# 20230322.net
KiCad netlist of a schematic drawn in EAGLE
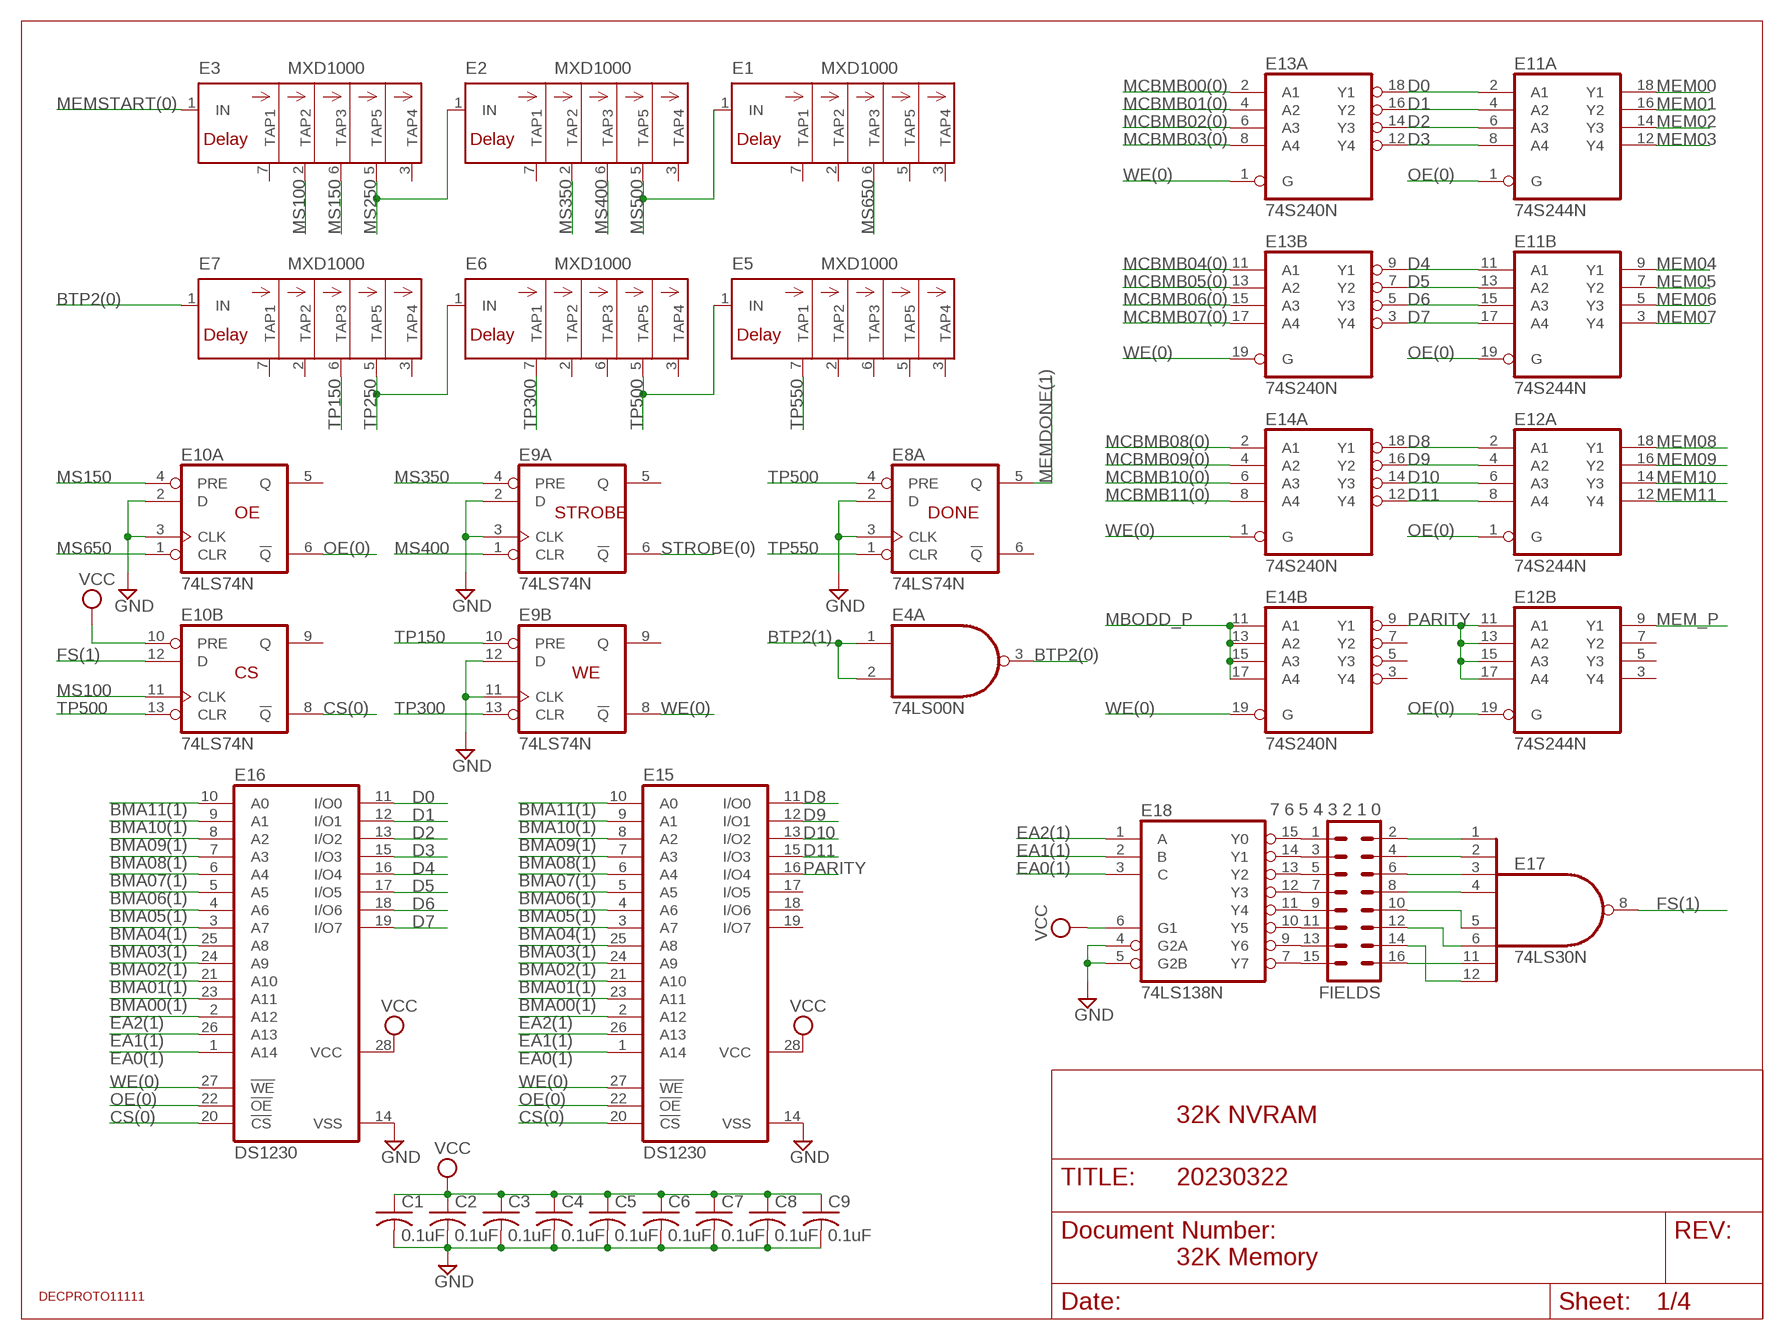
[diagram p0: schematic, sheet 1]
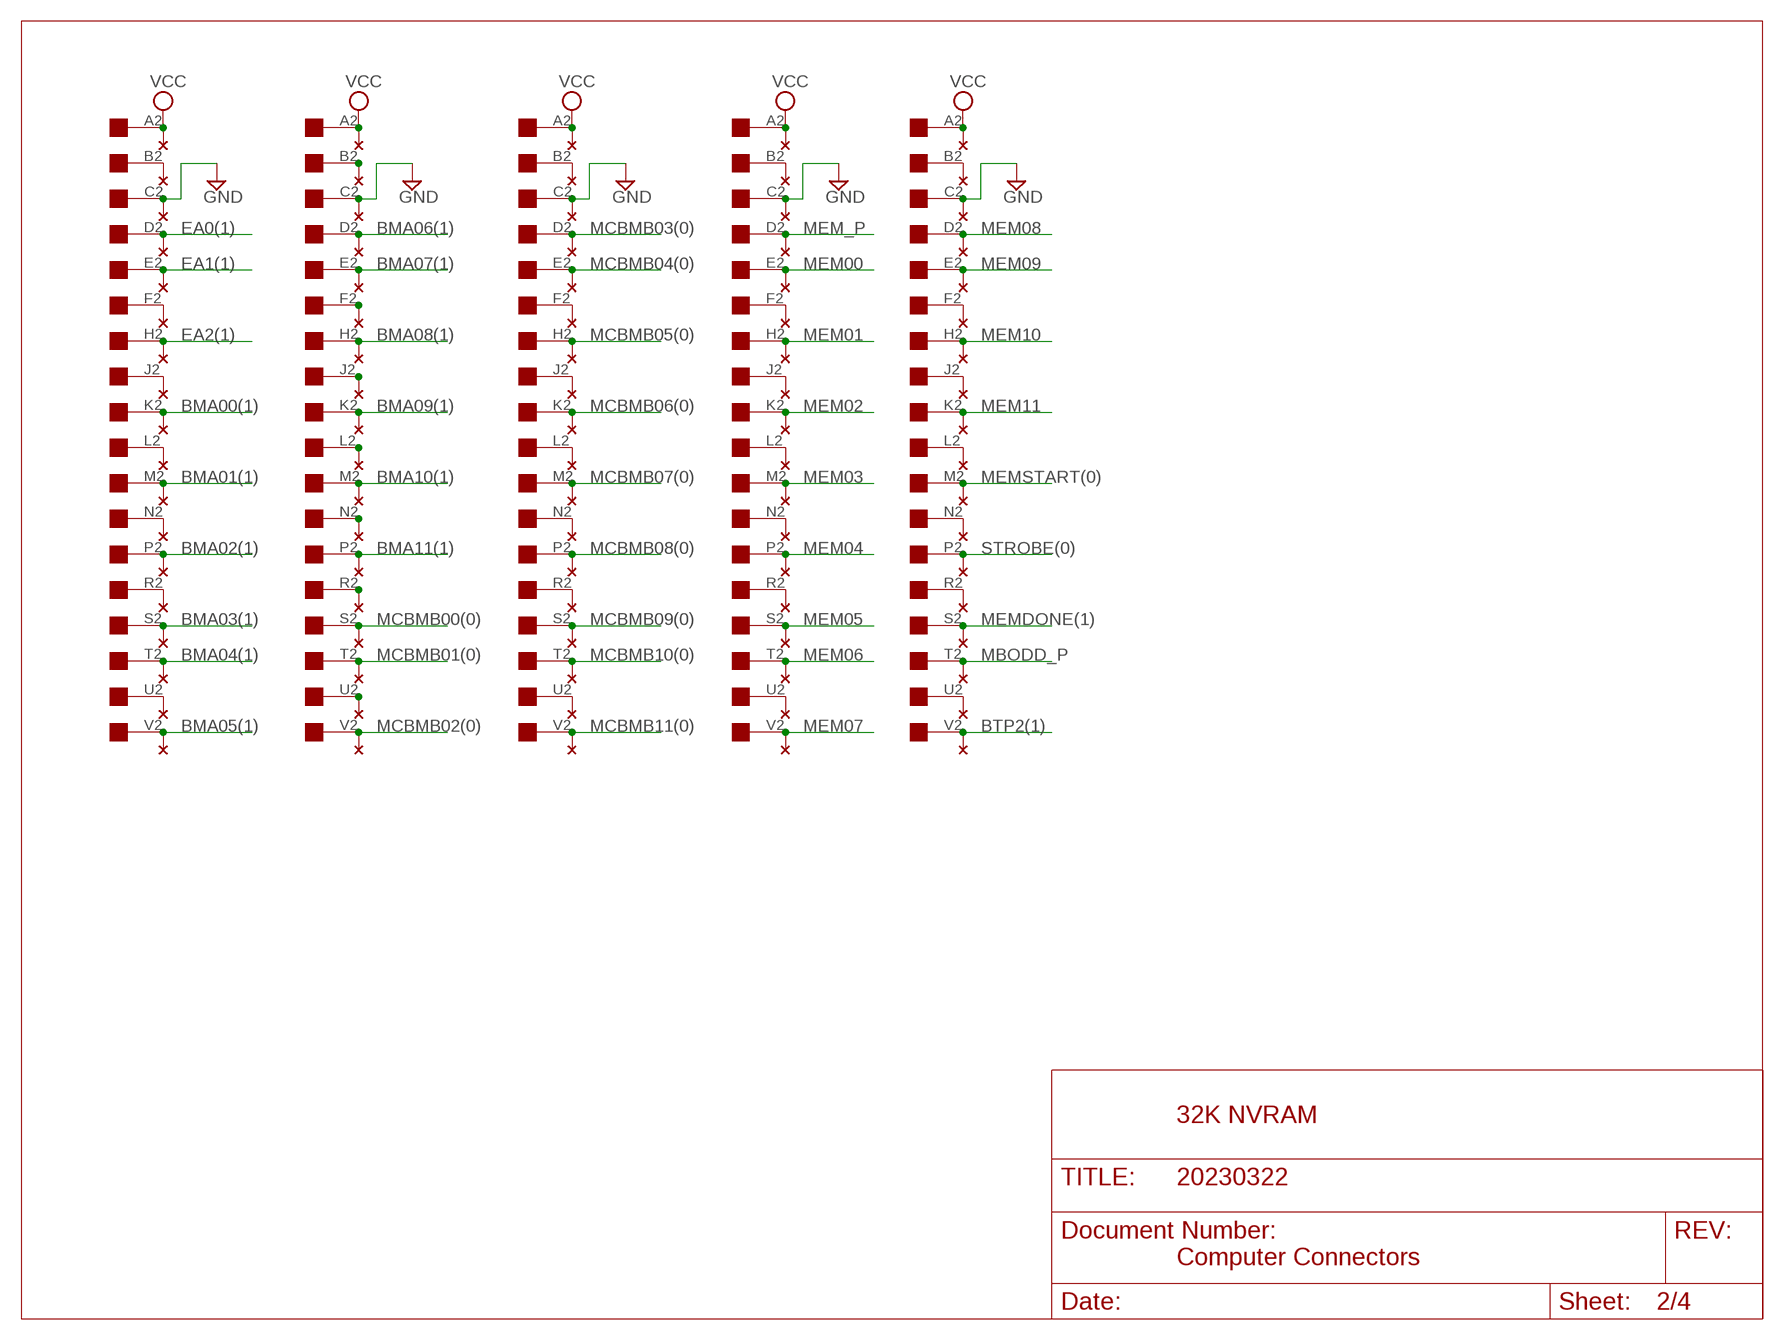
[diagram p1: schematic, sheet 2]
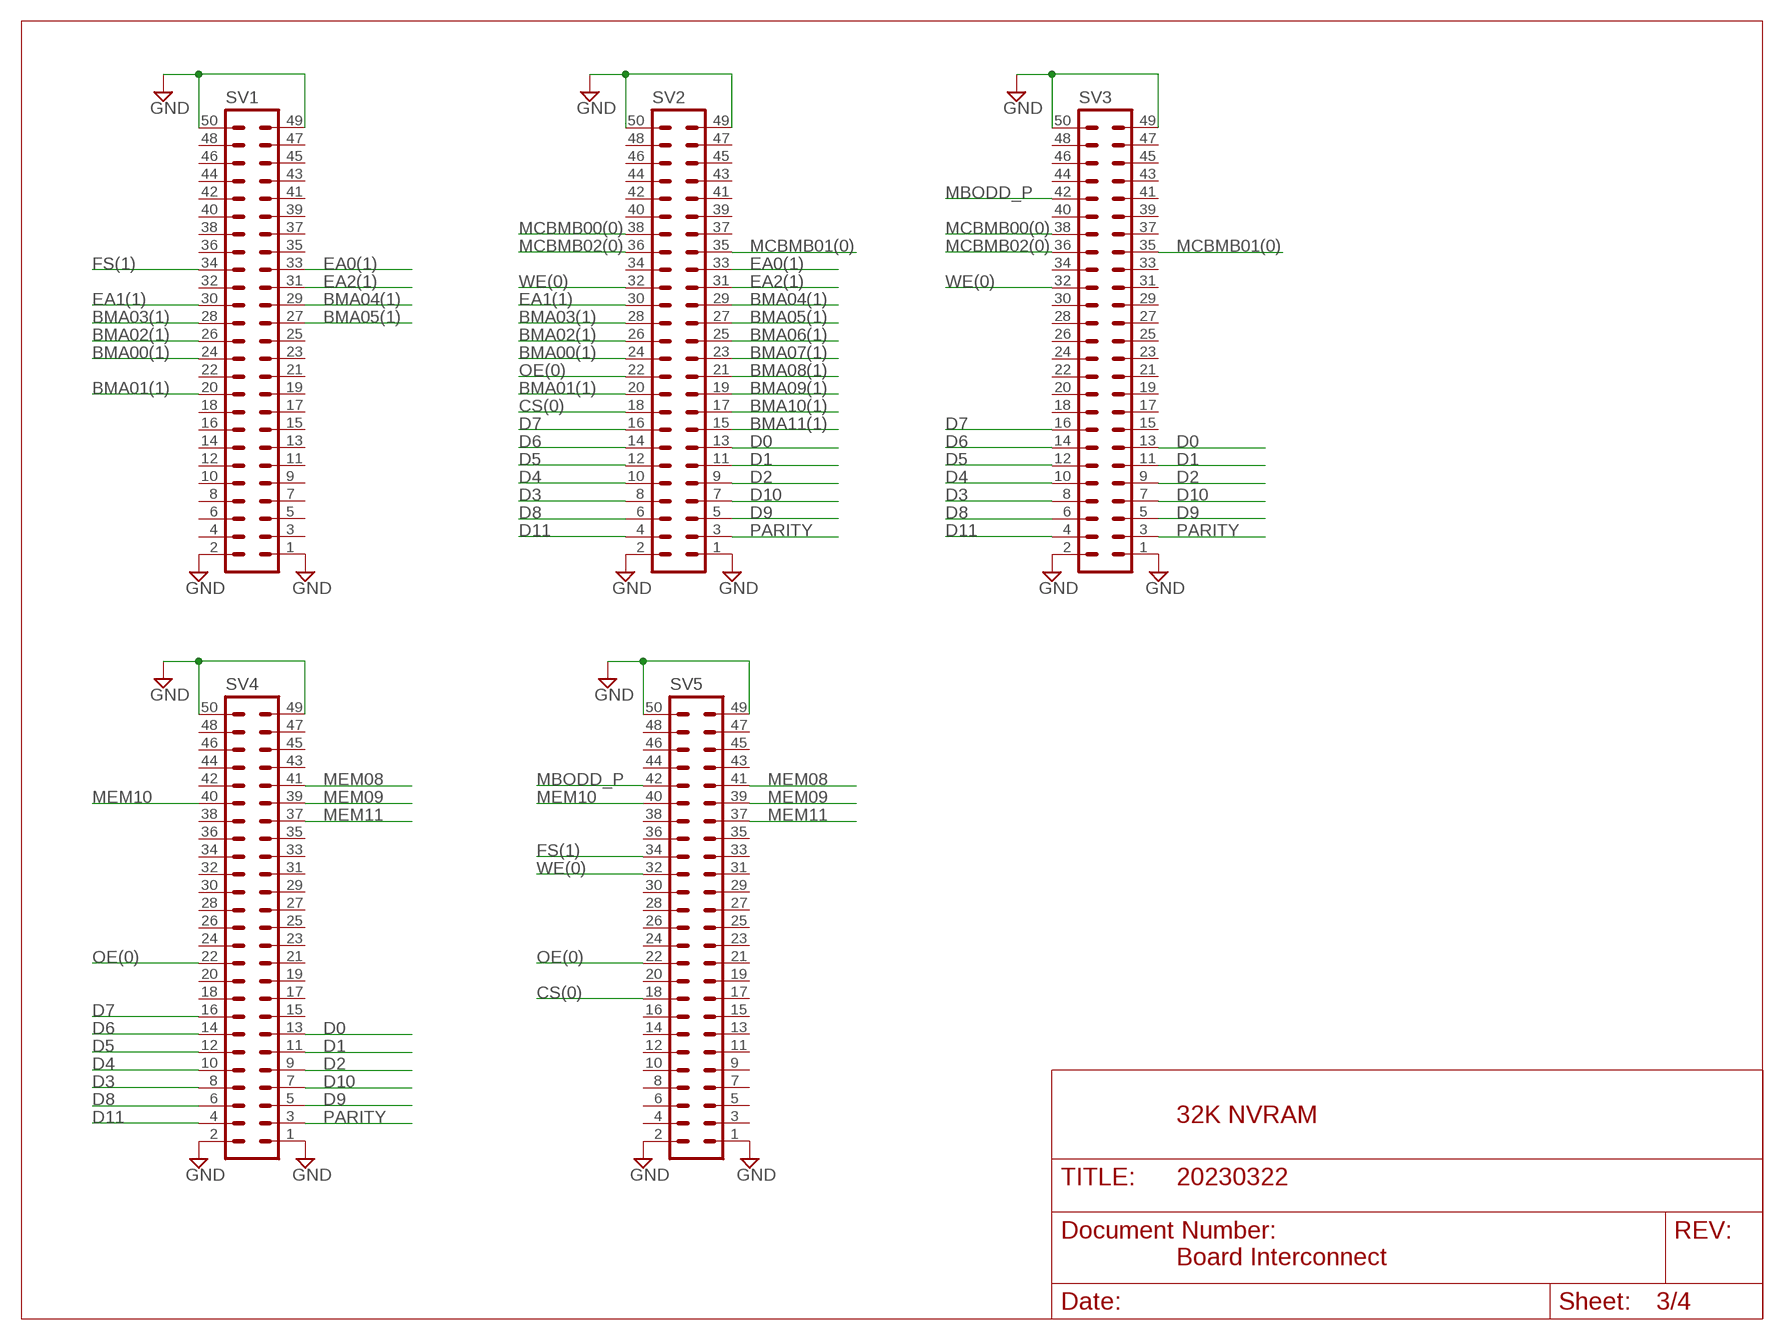
[diagram p2: schematic, sheet 3]
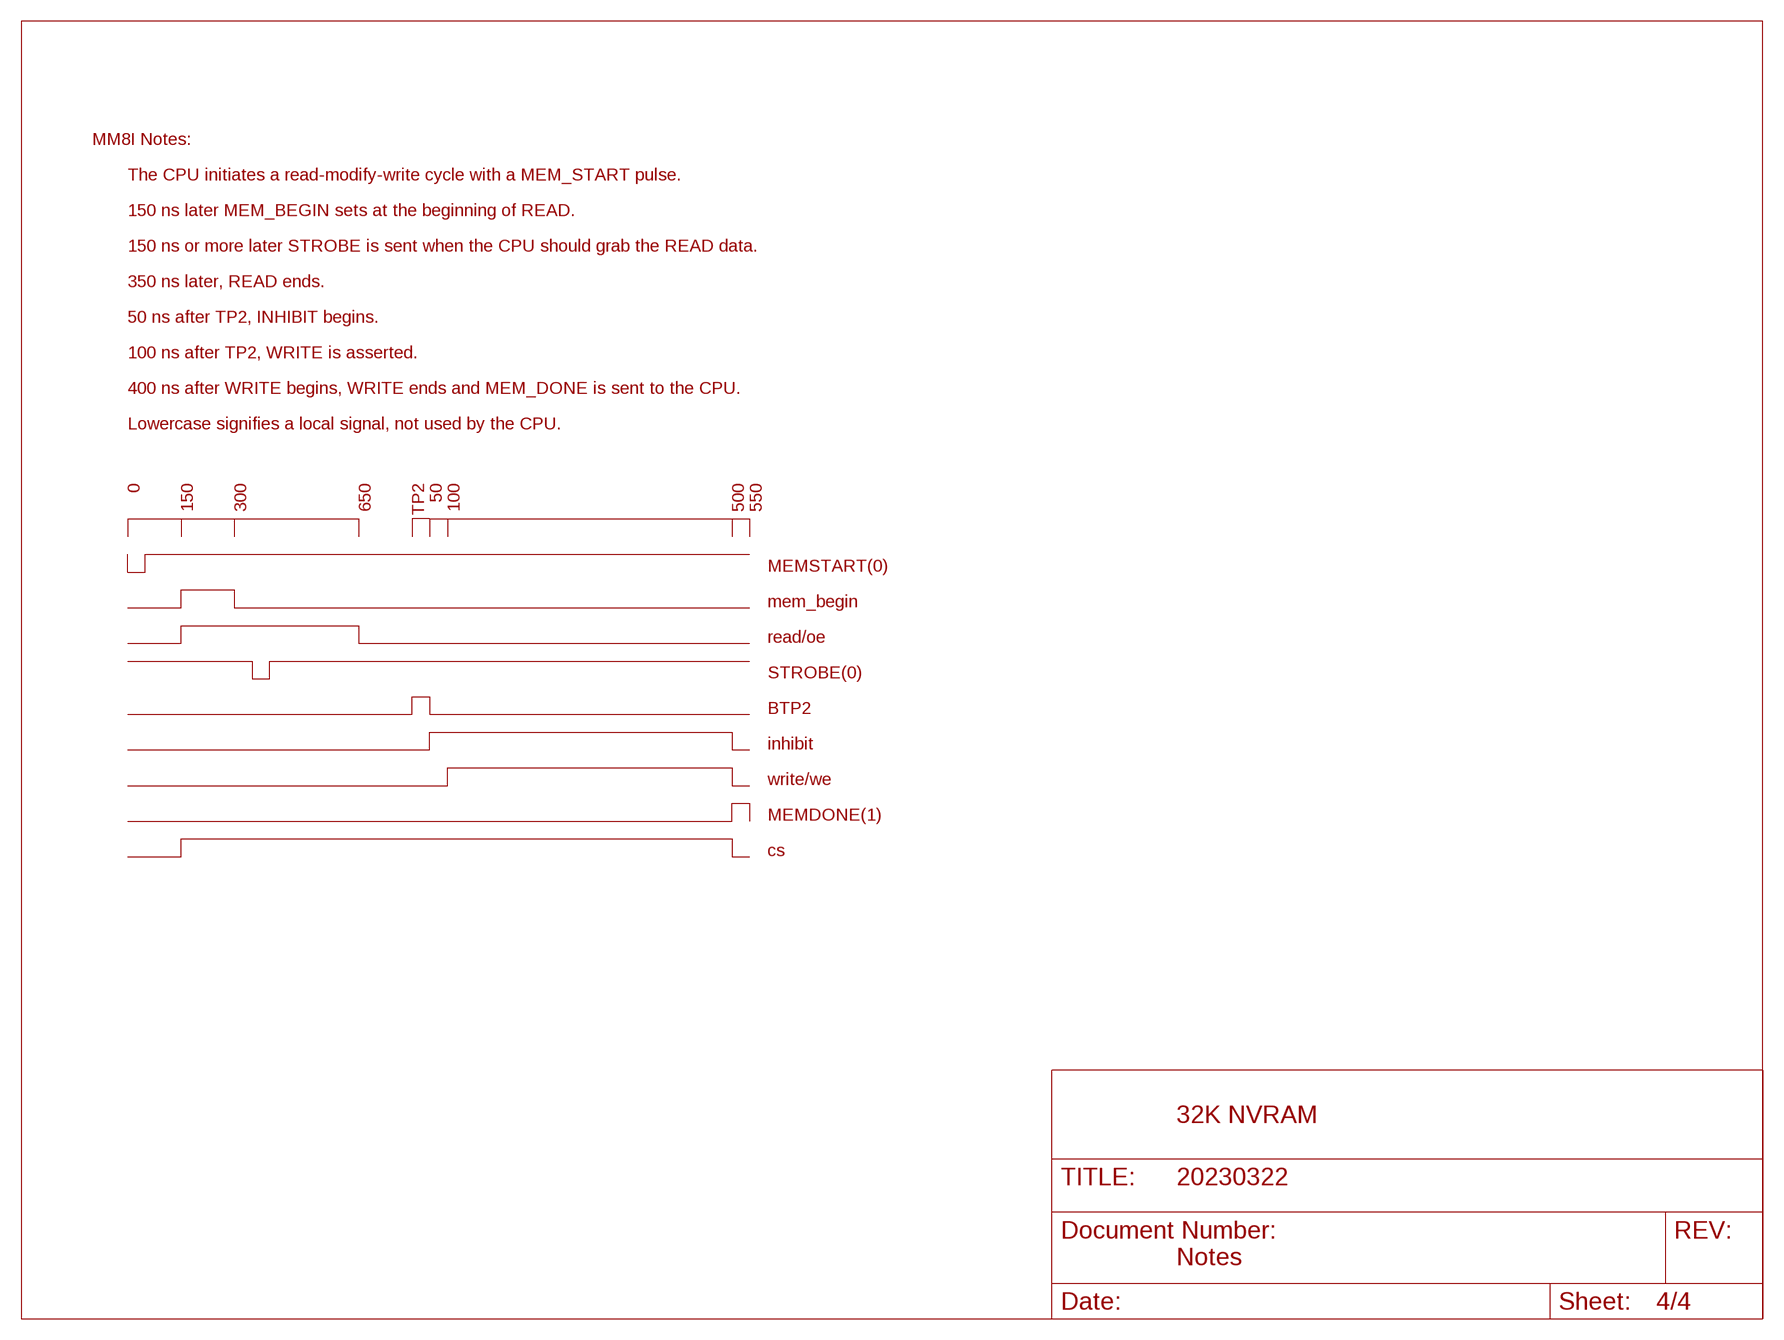
[diagram p3: schematic, sheet 4]

(export (version "E")
  (design (tool "Eeschema 10.0.6"))
  (components
    (comp (ref "H01")
      (value "EDGE-1")
      (footprint "eagle-import:EDGE-CON1")
      (libsource (lib "eagle-import") (part "EDGE-1"))
    )
    (comp (ref "H02")
      (value "EDGE-1")
      (footprint "eagle-import:EDGE-CON1")
      (libsource (lib "eagle-import") (part "EDGE-1"))
    )
    (comp (ref "H03")
      (value "EDGE-1")
      (footprint "eagle-import:EDGE-CON1")
      (libsource (lib "eagle-import") (part "EDGE-1"))
    )
    (comp (ref "H04")
      (value "EDGE-1")
      (footprint "eagle-import:EDGE-CON1")
      (libsource (lib "eagle-import") (part "EDGE-1"))
    )
    (comp (ref "H05")
      (value "EDGE-1")
      (footprint "eagle-import:EDGE-CON1")
      (libsource (lib "eagle-import") (part "EDGE-1"))
    )
    (comp (ref "U$1")
      (value "THRU-HOLE2")
      (footprint "eagle-import:THRU-HOLEB")
      (libsource (lib "eagle-import") (part "THRU-HOLE2"))
    )
    (comp (ref "U$2")
      (value "THRU-HOLE2")
      (footprint "eagle-import:THRU-HOLEB")
      (libsource (lib "eagle-import") (part "THRU-HOLE2"))
    )
    (comp (ref "U$3")
      (value "THRU-HOLE2")
      (footprint "eagle-import:THRU-HOLEB")
      (libsource (lib "eagle-import") (part "THRU-HOLE2"))
    )
    (comp (ref "U$4")
      (value "THRU-HOLE2")
      (footprint "eagle-import:THRU-HOLEB")
      (libsource (lib "eagle-import") (part "THRU-HOLE2"))
    )
    (comp (ref "U$5")
      (value "THRU-HOLE2")
      (footprint "eagle-import:THRU-HOLEB")
      (libsource (lib "eagle-import") (part "THRU-HOLE2"))
    )
    (comp (ref "SV1")
      (value "ML50L")
      (footprint "eagle-import:ML50L")
      (libsource (lib "eagle-import") (part "ML50L"))
    )
    (comp (ref "SV2")
      (value "ML50L")
      (footprint "eagle-import:ML50L")
      (libsource (lib "eagle-import") (part "ML50L"))
    )
    (comp (ref "SV3")
      (value "ML50L")
      (footprint "eagle-import:ML50L")
      (libsource (lib "eagle-import") (part "ML50L"))
    )
    (comp (ref "SV4")
      (value "ML50L")
      (footprint "eagle-import:ML50L")
      (libsource (lib "eagle-import") (part "ML50L"))
    )
    (comp (ref "SV5")
      (value "ML50L")
      (footprint "eagle-import:ML50L")
      (libsource (lib "eagle-import") (part "ML50L"))
    )
    (comp (ref "C1")
      (value "0.1uF")
      (footprint "eagle-import:C050-025X075")
      (libsource (lib "eagle-import") (part "C-US050-025X075"))
    )
    (comp (ref "C2")
      (value "0.1uF")
      (footprint "eagle-import:C050-025X075")
      (libsource (lib "eagle-import") (part "C-US050-025X075"))
    )
    (comp (ref "C3")
      (value "0.1uF")
      (footprint "eagle-import:C050-025X075")
      (libsource (lib "eagle-import") (part "C-US050-025X075"))
    )
    (comp (ref "C4")
      (value "0.1uF")
      (footprint "eagle-import:C050-025X075")
      (libsource (lib "eagle-import") (part "C-US050-025X075"))
    )
    (comp (ref "C5")
      (value "0.1uF")
      (footprint "eagle-import:C050-025X075")
      (libsource (lib "eagle-import") (part "C-US050-025X075"))
    )
    (comp (ref "C6")
      (value "0.1uF")
      (footprint "eagle-import:C050-025X075")
      (libsource (lib "eagle-import") (part "C-US050-025X075"))
    )
    (comp (ref "C7")
      (value "0.1uF")
      (footprint "eagle-import:C050-025X075")
      (libsource (lib "eagle-import") (part "C-US050-025X075"))
    )
    (comp (ref "C8")
      (value "0.1uF")
      (footprint "eagle-import:C050-025X075")
      (libsource (lib "eagle-import") (part "C-US050-025X075"))
    )
    (comp (ref "C9")
      (value "0.1uF")
      (footprint "eagle-import:C050-025X075")
      (libsource (lib "eagle-import") (part "C-US050-025X075"))
    )
    (comp (ref "E1")
      (value "MXD1000")
      (footprint "eagle-import:DIL08")
      (libsource (lib "eagle-import") (part "MXD1000"))
    )
    (comp (ref "E2")
      (value "MXD1000")
      (footprint "eagle-import:DIL08")
      (libsource (lib "eagle-import") (part "MXD1000"))
    )
    (comp (ref "E3")
      (value "MXD1000")
      (footprint "eagle-import:DIL08")
      (libsource (lib "eagle-import") (part "MXD1000"))
    )
    (comp (ref "E4")
      (value "74LS00N")
      (footprint "eagle-import:DIL14")
      (libsource (lib "eagle-import") (part "7400NLS"))
    )
    (comp (ref "E5")
      (value "MXD1000")
      (footprint "eagle-import:DIL08")
      (libsource (lib "eagle-import") (part "MXD1000"))
    )
    (comp (ref "E6")
      (value "MXD1000")
      (footprint "eagle-import:DIL08")
      (libsource (lib "eagle-import") (part "MXD1000"))
    )
    (comp (ref "E7")
      (value "MXD1000")
      (footprint "eagle-import:DIL08")
      (libsource (lib "eagle-import") (part "MXD1000"))
    )
    (comp (ref "E8")
      (value "74LS74N")
      (footprint "eagle-import:DIL14")
      (libsource (lib "eagle-import") (part "7474NLS"))
    )
    (comp (ref "E9")
      (value "74LS74N")
      (footprint "eagle-import:DIL14")
      (libsource (lib "eagle-import") (part "7474NLS"))
    )
    (comp (ref "E10")
      (value "74LS74N")
      (footprint "eagle-import:DIL14")
      (libsource (lib "eagle-import") (part "7474NLS"))
    )
    (comp (ref "E11")
      (value "74S244N")
      (footprint "eagle-import:DIL20")
      (libsource (lib "eagle-import") (part "74244NS"))
    )
    (comp (ref "E12")
      (value "74S244N")
      (footprint "eagle-import:DIL20")
      (libsource (lib "eagle-import") (part "74244NS"))
    )
    (comp (ref "E13")
      (value "74S240N")
      (footprint "eagle-import:DIL20")
      (libsource (lib "eagle-import") (part "74240NS"))
    )
    (comp (ref "E14")
      (value "74S240N")
      (footprint "eagle-import:DIL20")
      (libsource (lib "eagle-import") (part "74240NS"))
    )
    (comp (ref "E15")
      (value "DS1230")
      (footprint "eagle-import:DIL28-6")
      (libsource (lib "eagle-import") (part "62256P"))
    )
    (comp (ref "E16")
      (value "DS1230")
      (footprint "eagle-import:DIL28-6")
      (libsource (lib "eagle-import") (part "62256P"))
    )
    (comp (ref "E17")
      (value "74LS30N")
      (footprint "eagle-import:DIL14")
      (libsource (lib "eagle-import") (part "7430NLS"))
    )
    (comp (ref "E18")
      (value "74LS138N")
      (footprint "eagle-import:DIL16")
      (libsource (lib "eagle-import") (part "74138NLS"))
    )
    (comp (ref "FIELDS")
      (value "7 6 5 4 3 2 1 0")
      (footprint "eagle-import:MA08-2")
      (libsource (lib "eagle-import") (part "MA08-2"))
    )
    (comp (ref "U$6")
      (value "DECPROTO11111")
      (footprint "eagle-import:DECPROTO11111")
      (libsource (lib "eagle-import") (part "DECPROTO11111"))
    )
  )
  (nets
    (net (code "1") (name "BMA00(1)") (class "Default")
      (node (ref "E15") (pin "23") (pinfunction "A11_23") (pintype "input"))
      (node (ref "E16") (pin "23") (pinfunction "A11_23") (pintype "input"))
      (node (ref "H01") (pin "K2") (pinfunction "1_K2") (pintype "bidirectional"))
      (node (ref "SV1") (pin "24") (pinfunction "24_24") (pintype "passive"))
      (node (ref "SV2") (pin "24") (pinfunction "24_24") (pintype "passive"))
      (node (ref "U$1") (pin "K2") (pinfunction "P$1_K2") (pintype "passive"))
    )
    (net (code "2") (name "BMA01(1)") (class "Default")
      (node (ref "E15") (pin "21") (pinfunction "A10_21") (pintype "input"))
      (node (ref "E16") (pin "21") (pinfunction "A10_21") (pintype "input"))
      (node (ref "H01") (pin "M2") (pinfunction "1_M2") (pintype "bidirectional"))
      (node (ref "SV1") (pin "20") (pinfunction "20_20") (pintype "passive"))
      (node (ref "SV2") (pin "20") (pinfunction "20_20") (pintype "passive"))
      (node (ref "U$1") (pin "M2") (pinfunction "P$1_M2") (pintype "passive"))
    )
    (net (code "3") (name "BMA02(1)") (class "Default")
      (node (ref "E15") (pin "24") (pinfunction "A9_24") (pintype "input"))
      (node (ref "E16") (pin "24") (pinfunction "A9_24") (pintype "input"))
      (node (ref "H01") (pin "P2") (pinfunction "1_P2") (pintype "bidirectional"))
      (node (ref "SV1") (pin "26") (pinfunction "26_26") (pintype "passive"))
      (node (ref "SV2") (pin "26") (pinfunction "26_26") (pintype "passive"))
      (node (ref "U$1") (pin "P2") (pinfunction "P$1_P2") (pintype "passive"))
    )
    (net (code "4") (name "BMA03(1)") (class "Default")
      (node (ref "E15") (pin "25") (pinfunction "A8_25") (pintype "input"))
      (node (ref "E16") (pin "25") (pinfunction "A8_25") (pintype "input"))
      (node (ref "H01") (pin "S2") (pinfunction "1_S2") (pintype "bidirectional"))
      (node (ref "SV1") (pin "28") (pinfunction "28_28") (pintype "passive"))
      (node (ref "SV2") (pin "28") (pinfunction "28_28") (pintype "passive"))
      (node (ref "U$1") (pin "S2") (pinfunction "P$1_S2") (pintype "passive"))
    )
    (net (code "5") (name "BMA04(1)") (class "Default")
      (node (ref "E15") (pin "3") (pinfunction "A7_3") (pintype "input"))
      (node (ref "E16") (pin "3") (pinfunction "A7_3") (pintype "input"))
      (node (ref "H01") (pin "T2") (pinfunction "1_T2") (pintype "bidirectional"))
      (node (ref "SV1") (pin "29") (pinfunction "29_29") (pintype "passive"))
      (node (ref "SV2") (pin "29") (pinfunction "29_29") (pintype "passive"))
      (node (ref "U$1") (pin "T2") (pinfunction "P$1_T2") (pintype "passive"))
    )
    (net (code "6") (name "BMA05(1)") (class "Default")
      (node (ref "E15") (pin "4") (pinfunction "A6_4") (pintype "input"))
      (node (ref "E16") (pin "4") (pinfunction "A6_4") (pintype "input"))
      (node (ref "H01") (pin "V2") (pinfunction "1_V2") (pintype "bidirectional"))
      (node (ref "SV1") (pin "27") (pinfunction "27_27") (pintype "passive"))
      (node (ref "SV2") (pin "27") (pinfunction "27_27") (pintype "passive"))
      (node (ref "U$1") (pin "V2") (pinfunction "P$1_V2") (pintype "passive"))
    )
    (net (code "7") (name "BMA06(1)") (class "Default")
      (node (ref "E15") (pin "5") (pinfunction "A5_5") (pintype "input"))
      (node (ref "E16") (pin "5") (pinfunction "A5_5") (pintype "input"))
      (node (ref "H02") (pin "D2") (pinfunction "1_D2") (pintype "bidirectional"))
      (node (ref "SV2") (pin "25") (pinfunction "25_25") (pintype "passive"))
      (node (ref "U$2") (pin "D2") (pinfunction "P$1_D2") (pintype "passive"))
    )
    (net (code "8") (name "BMA07(1)") (class "Default")
      (node (ref "E15") (pin "6") (pinfunction "A4_6") (pintype "input"))
      (node (ref "E16") (pin "6") (pinfunction "A4_6") (pintype "input"))
      (node (ref "H02") (pin "E2") (pinfunction "1_E2") (pintype "bidirectional"))
      (node (ref "SV2") (pin "23") (pinfunction "23_23") (pintype "passive"))
      (node (ref "U$2") (pin "E2") (pinfunction "P$1_E2") (pintype "passive"))
    )
    (net (code "9") (name "BMA08(1)") (class "Default")
      (node (ref "E15") (pin "7") (pinfunction "A3_7") (pintype "input"))
      (node (ref "E16") (pin "7") (pinfunction "A3_7") (pintype "input"))
      (node (ref "H02") (pin "H2") (pinfunction "1_H2") (pintype "bidirectional"))
      (node (ref "SV2") (pin "21") (pinfunction "21_21") (pintype "passive"))
      (node (ref "U$2") (pin "H2") (pinfunction "P$1_H2") (pintype "passive"))
    )
    (net (code "10") (name "BMA09(1)") (class "Default")
      (node (ref "E15") (pin "8") (pinfunction "A2_8") (pintype "input"))
      (node (ref "E16") (pin "8") (pinfunction "A2_8") (pintype "input"))
      (node (ref "H02") (pin "K2") (pinfunction "1_K2") (pintype "bidirectional"))
      (node (ref "SV2") (pin "19") (pinfunction "19_19") (pintype "passive"))
      (node (ref "U$2") (pin "K2") (pinfunction "P$1_K2") (pintype "passive"))
    )
    (net (code "11") (name "BMA10(1)") (class "Default")
      (node (ref "E15") (pin "9") (pinfunction "A1_9") (pintype "input"))
      (node (ref "E16") (pin "9") (pinfunction "A1_9") (pintype "input"))
      (node (ref "H02") (pin "M2") (pinfunction "1_M2") (pintype "bidirectional"))
      (node (ref "SV2") (pin "17") (pinfunction "17_17") (pintype "passive"))
      (node (ref "U$2") (pin "M2") (pinfunction "P$1_M2") (pintype "passive"))
    )
    (net (code "12") (name "BMA11(1)") (class "Default")
      (node (ref "E15") (pin "10") (pinfunction "A0_10") (pintype "input"))
      (node (ref "E16") (pin "10") (pinfunction "A0_10") (pintype "input"))
      (node (ref "H02") (pin "P2") (pinfunction "1_P2") (pintype "bidirectional"))
      (node (ref "SV2") (pin "15") (pinfunction "15_15") (pintype "passive"))
      (node (ref "U$2") (pin "P2") (pinfunction "P$1_P2") (pintype "passive"))
    )
    (net (code "13") (name "BTP2(0)") (class "Default")
      (node (ref "E4") (pin "3") (pinfunction "O_3") (pintype "output"))
      (node (ref "E7") (pin "1") (pinfunction "IN_1") (pintype "input"))
    )
    (net (code "14") (name "BTP2(1)") (class "Default")
      (node (ref "E4") (pin "1") (pinfunction "I0_1") (pintype "input"))
      (node (ref "E4") (pin "2") (pinfunction "I1_2") (pintype "input"))
      (node (ref "H05") (pin "V2") (pinfunction "1_V2") (pintype "bidirectional"))
      (node (ref "U$5") (pin "V2") (pinfunction "P$1_V2") (pintype "passive"))
    )
    (net (code "15") (name "CS(0)") (class "Default")
      (node (ref "E10") (pin "8") (pinfunction "~{Q}_8") (pintype "output"))
      (node (ref "E15") (pin "20") (pinfunction "~{CS}_20") (pintype "input"))
      (node (ref "E16") (pin "20") (pinfunction "~{CS}_20") (pintype "input"))
      (node (ref "SV2") (pin "18") (pinfunction "18_18") (pintype "passive"))
      (node (ref "SV5") (pin "18") (pinfunction "18_18") (pintype "passive"))
    )
    (net (code "16") (name "D0") (class "Default")
      (node (ref "E11") (pin "2") (pinfunction "A1_2") (pintype "input"))
      (node (ref "E13") (pin "18") (pinfunction "Y1_18") (pintype "tri_state"))
      (node (ref "E16") (pin "11") (pinfunction "I/O0_11") (pintype "bidirectional"))
      (node (ref "SV2") (pin "13") (pinfunction "13_13") (pintype "passive"))
      (node (ref "SV3") (pin "13") (pinfunction "13_13") (pintype "passive"))
      (node (ref "SV4") (pin "13") (pinfunction "13_13") (pintype "passive"))
    )
    (net (code "17") (name "D1") (class "Default")
      (node (ref "E11") (pin "4") (pinfunction "A2_4") (pintype "input"))
      (node (ref "E13") (pin "16") (pinfunction "Y2_16") (pintype "tri_state"))
      (node (ref "E16") (pin "12") (pinfunction "I/O1_12") (pintype "bidirectional"))
      (node (ref "SV2") (pin "11") (pinfunction "11_11") (pintype "passive"))
      (node (ref "SV3") (pin "11") (pinfunction "11_11") (pintype "passive"))
      (node (ref "SV4") (pin "11") (pinfunction "11_11") (pintype "passive"))
    )
    (net (code "18") (name "D2") (class "Default")
      (node (ref "E11") (pin "6") (pinfunction "A3_6") (pintype "input"))
      (node (ref "E13") (pin "14") (pinfunction "Y3_14") (pintype "tri_state"))
      (node (ref "E16") (pin "13") (pinfunction "I/O2_13") (pintype "bidirectional"))
      (node (ref "SV2") (pin "9") (pinfunction "9_9") (pintype "passive"))
      (node (ref "SV3") (pin "9") (pinfunction "9_9") (pintype "passive"))
      (node (ref "SV4") (pin "9") (pinfunction "9_9") (pintype "passive"))
    )
    (net (code "19") (name "D3") (class "Default")
      (node (ref "E11") (pin "8") (pinfunction "A4_8") (pintype "input"))
      (node (ref "E13") (pin "12") (pinfunction "Y4_12") (pintype "tri_state"))
      (node (ref "E16") (pin "15") (pinfunction "I/O3_15") (pintype "bidirectional"))
      (node (ref "SV2") (pin "8") (pinfunction "8_8") (pintype "passive"))
      (node (ref "SV3") (pin "8") (pinfunction "8_8") (pintype "passive"))
      (node (ref "SV4") (pin "8") (pinfunction "8_8") (pintype "passive"))
    )
    (net (code "20") (name "D4") (class "Default")
      (node (ref "E11") (pin "11") (pinfunction "A1_11") (pintype "input"))
      (node (ref "E13") (pin "9") (pinfunction "Y1_9") (pintype "tri_state"))
      (node (ref "E16") (pin "16") (pinfunction "I/O4_16") (pintype "bidirectional"))
      (node (ref "SV2") (pin "10") (pinfunction "10_10") (pintype "passive"))
      (node (ref "SV3") (pin "10") (pinfunction "10_10") (pintype "passive"))
      (node (ref "SV4") (pin "10") (pinfunction "10_10") (pintype "passive"))
    )
    (net (code "21") (name "D5") (class "Default")
      (node (ref "E11") (pin "13") (pinfunction "A2_13") (pintype "input"))
      (node (ref "E13") (pin "7") (pinfunction "Y2_7") (pintype "tri_state"))
      (node (ref "E16") (pin "17") (pinfunction "I/O5_17") (pintype "bidirectional"))
      (node (ref "SV2") (pin "12") (pinfunction "12_12") (pintype "passive"))
      (node (ref "SV3") (pin "12") (pinfunction "12_12") (pintype "passive"))
      (node (ref "SV4") (pin "12") (pinfunction "12_12") (pintype "passive"))
    )
    (net (code "22") (name "D6") (class "Default")
      (node (ref "E11") (pin "15") (pinfunction "A3_15") (pintype "input"))
      (node (ref "E13") (pin "5") (pinfunction "Y3_5") (pintype "tri_state"))
      (node (ref "E16") (pin "18") (pinfunction "I/O6_18") (pintype "bidirectional"))
      (node (ref "SV2") (pin "14") (pinfunction "14_14") (pintype "passive"))
      (node (ref "SV3") (pin "14") (pinfunction "14_14") (pintype "passive"))
      (node (ref "SV4") (pin "14") (pinfunction "14_14") (pintype "passive"))
    )
    (net (code "23") (name "D7") (class "Default")
      (node (ref "E11") (pin "17") (pinfunction "A4_17") (pintype "input"))
      (node (ref "E13") (pin "3") (pinfunction "Y4_3") (pintype "tri_state"))
      (node (ref "E16") (pin "19") (pinfunction "I/O7_19") (pintype "bidirectional"))
      (node (ref "SV2") (pin "16") (pinfunction "16_16") (pintype "passive"))
      (node (ref "SV3") (pin "16") (pinfunction "16_16") (pintype "passive"))
      (node (ref "SV4") (pin "16") (pinfunction "16_16") (pintype "passive"))
    )
    (net (code "24") (name "D8") (class "Default")
      (node (ref "E12") (pin "2") (pinfunction "A1_2") (pintype "input"))
      (node (ref "E14") (pin "18") (pinfunction "Y1_18") (pintype "tri_state"))
      (node (ref "E15") (pin "11") (pinfunction "I/O0_11") (pintype "bidirectional"))
      (node (ref "SV2") (pin "6") (pinfunction "6_6") (pintype "passive"))
      (node (ref "SV3") (pin "6") (pinfunction "6_6") (pintype "passive"))
      (node (ref "SV4") (pin "6") (pinfunction "6_6") (pintype "passive"))
    )
    (net (code "25") (name "D9") (class "Default")
      (node (ref "E12") (pin "4") (pinfunction "A2_4") (pintype "input"))
      (node (ref "E14") (pin "16") (pinfunction "Y2_16") (pintype "tri_state"))
      (node (ref "E15") (pin "12") (pinfunction "I/O1_12") (pintype "bidirectional"))
      (node (ref "SV2") (pin "5") (pinfunction "5_5") (pintype "passive"))
      (node (ref "SV3") (pin "5") (pinfunction "5_5") (pintype "passive"))
      (node (ref "SV4") (pin "5") (pinfunction "5_5") (pintype "passive"))
    )
    (net (code "26") (name "D10") (class "Default")
      (node (ref "E12") (pin "6") (pinfunction "A3_6") (pintype "input"))
      (node (ref "E14") (pin "14") (pinfunction "Y3_14") (pintype "tri_state"))
      (node (ref "E15") (pin "13") (pinfunction "I/O2_13") (pintype "bidirectional"))
      (node (ref "SV2") (pin "7") (pinfunction "7_7") (pintype "passive"))
      (node (ref "SV3") (pin "7") (pinfunction "7_7") (pintype "passive"))
      (node (ref "SV4") (pin "7") (pinfunction "7_7") (pintype "passive"))
    )
    (net (code "27") (name "D11") (class "Default")
      (node (ref "E12") (pin "8") (pinfunction "A4_8") (pintype "input"))
      (node (ref "E14") (pin "12") (pinfunction "Y4_12") (pintype "tri_state"))
      (node (ref "E15") (pin "15") (pinfunction "I/O3_15") (pintype "bidirectional"))
      (node (ref "SV2") (pin "4") (pinfunction "4_4") (pintype "passive"))
      (node (ref "SV3") (pin "4") (pinfunction "4_4") (pintype "passive"))
      (node (ref "SV4") (pin "4") (pinfunction "4_4") (pintype "passive"))
    )
    (net (code "28") (name "EA0(1)") (class "Default")
      (node (ref "E15") (pin "1") (pinfunction "A14_1") (pintype "input"))
      (node (ref "E16") (pin "1") (pinfunction "A14_1") (pintype "input"))
      (node (ref "E18") (pin "3") (pinfunction "C_3") (pintype "input"))
      (node (ref "H01") (pin "D2") (pinfunction "1_D2") (pintype "bidirectional"))
      (node (ref "SV1") (pin "33") (pinfunction "33_33") (pintype "passive"))
      (node (ref "SV2") (pin "33") (pinfunction "33_33") (pintype "passive"))
      (node (ref "U$1") (pin "D2") (pinfunction "P$1_D2") (pintype "passive"))
    )
    (net (code "29") (name "EA1(1)") (class "Default")
      (node (ref "E15") (pin "26") (pinfunction "A13_26") (pintype "input"))
      (node (ref "E16") (pin "26") (pinfunction "A13_26") (pintype "input"))
      (node (ref "E18") (pin "2") (pinfunction "B_2") (pintype "input"))
      (node (ref "H01") (pin "E2") (pinfunction "1_E2") (pintype "bidirectional"))
      (node (ref "SV1") (pin "30") (pinfunction "30_30") (pintype "passive"))
      (node (ref "SV2") (pin "30") (pinfunction "30_30") (pintype "passive"))
      (node (ref "U$1") (pin "E2") (pinfunction "P$1_E2") (pintype "passive"))
    )
    (net (code "30") (name "EA2(1)") (class "Default")
      (node (ref "E15") (pin "2") (pinfunction "A12_2") (pintype "input"))
      (node (ref "E16") (pin "2") (pinfunction "A12_2") (pintype "input"))
      (node (ref "E18") (pin "1") (pinfunction "A_1") (pintype "input"))
      (node (ref "H01") (pin "H2") (pinfunction "1_H2") (pintype "bidirectional"))
      (node (ref "SV1") (pin "31") (pinfunction "31_31") (pintype "passive"))
      (node (ref "SV2") (pin "31") (pinfunction "31_31") (pintype "passive"))
      (node (ref "U$1") (pin "H2") (pinfunction "P$1_H2") (pintype "passive"))
    )
    (net (code "31") (name "FS(1)") (class "Default")
      (node (ref "E10") (pin "12") (pinfunction "D_12") (pintype "input"))
      (node (ref "E17") (pin "8") (pinfunction "O_8") (pintype "output"))
      (node (ref "SV1") (pin "34") (pinfunction "34_34") (pintype "passive"))
      (node (ref "SV5") (pin "34") (pinfunction "34_34") (pintype "passive"))
    )
    (net (code "32") (name "GND") (class "Default")
      (node (ref "C1") (pin "2") (pinfunction "2_2") (pintype "passive"))
      (node (ref "C2") (pin "2") (pinfunction "2_2") (pintype "passive"))
      (node (ref "C3") (pin "2") (pinfunction "2_2") (pintype "passive"))
      (node (ref "C4") (pin "2") (pinfunction "2_2") (pintype "passive"))
      (node (ref "C5") (pin "2") (pinfunction "2_2") (pintype "passive"))
      (node (ref "C6") (pin "2") (pinfunction "2_2") (pintype "passive"))
      (node (ref "C7") (pin "2") (pinfunction "2_2") (pintype "passive"))
      (node (ref "C8") (pin "2") (pinfunction "2_2") (pintype "passive"))
      (node (ref "C9") (pin "2") (pinfunction "2_2") (pintype "passive"))
      (node (ref "E10") (pin "2") (pinfunction "D_2") (pintype "input"))
      (node (ref "E10") (pin "3") (pinfunction "CLK_3") (pintype "input"))
      (node (ref "E15") (pin "14") (pinfunction "VSS_14") (pintype "power_in"))
      (node (ref "E16") (pin "14") (pinfunction "VSS_14") (pintype "power_in"))
      (node (ref "E18") (pin "4") (pinfunction "G2A_4") (pintype "input"))
      (node (ref "E18") (pin "5") (pinfunction "G2B_5") (pintype "input"))
      (node (ref "E8") (pin "2") (pinfunction "D_2") (pintype "input"))
      (node (ref "E8") (pin "3") (pinfunction "CLK_3") (pintype "input"))
      (node (ref "E9") (pin "11") (pinfunction "CLK_11") (pintype "input"))
      (node (ref "E9") (pin "12") (pinfunction "D_12") (pintype "input"))
      (node (ref "E9") (pin "2") (pinfunction "D_2") (pintype "input"))
      (node (ref "E9") (pin "3") (pinfunction "CLK_3") (pintype "input"))
      (node (ref "H01") (pin "C2") (pinfunction "1_C2") (pintype "bidirectional"))
      (node (ref "H02") (pin "C2") (pinfunction "1_C2") (pintype "bidirectional"))
      (node (ref "H03") (pin "C2") (pinfunction "1_C2") (pintype "bidirectional"))
      (node (ref "H04") (pin "C2") (pinfunction "1_C2") (pintype "bidirectional"))
      (node (ref "H05") (pin "C2") (pinfunction "1_C2") (pintype "bidirectional"))
      (node (ref "SV1") (pin "1") (pinfunction "1_1") (pintype "passive"))
      (node (ref "SV1") (pin "2") (pinfunction "2_2") (pintype "passive"))
      (node (ref "SV1") (pin "49") (pinfunction "49_49") (pintype "passive"))
      (node (ref "SV1") (pin "50") (pinfunction "50_50") (pintype "passive"))
      (node (ref "SV2") (pin "1") (pinfunction "1_1") (pintype "passive"))
      (node (ref "SV2") (pin "2") (pinfunction "2_2") (pintype "passive"))
      (node (ref "SV2") (pin "49") (pinfunction "49_49") (pintype "passive"))
      (node (ref "SV2") (pin "50") (pinfunction "50_50") (pintype "passive"))
      (node (ref "SV3") (pin "1") (pinfunction "1_1") (pintype "passive"))
      (node (ref "SV3") (pin "2") (pinfunction "2_2") (pintype "passive"))
      (node (ref "SV3") (pin "49") (pinfunction "49_49") (pintype "passive"))
      (node (ref "SV3") (pin "50") (pinfunction "50_50") (pintype "passive"))
      (node (ref "SV4") (pin "1") (pinfunction "1_1") (pintype "passive"))
      (node (ref "SV4") (pin "2") (pinfunction "2_2") (pintype "passive"))
      (node (ref "SV4") (pin "49") (pinfunction "49_49") (pintype "passive"))
      (node (ref "SV4") (pin "50") (pinfunction "50_50") (pintype "passive"))
      (node (ref "SV5") (pin "1") (pinfunction "1_1") (pintype "passive"))
      (node (ref "SV5") (pin "2") (pinfunction "2_2") (pintype "passive"))
      (node (ref "SV5") (pin "49") (pinfunction "49_49") (pintype "passive"))
      (node (ref "SV5") (pin "50") (pinfunction "50_50") (pintype "passive"))
      (node (ref "U$1") (pin "C2") (pinfunction "P$1_C2") (pintype "passive"))
      (node (ref "U$2") (pin "C2") (pinfunction "P$1_C2") (pintype "passive"))
      (node (ref "U$3") (pin "C2") (pinfunction "P$1_C2") (pintype "passive"))
      (node (ref "U$4") (pin "C2") (pinfunction "P$1_C2") (pintype "passive"))
      (node (ref "U$5") (pin "C2") (pinfunction "P$1_C2") (pintype "passive"))
    )
    (net (code "33") (name "MBODD_P") (class "Default")
      (node (ref "E14") (pin "11") (pinfunction "A1_11") (pintype "input"))
      (node (ref "E14") (pin "13") (pinfunction "A2_13") (pintype "input"))
      (node (ref "E14") (pin "15") (pinfunction "A3_15") (pintype "input"))
      (node (ref "E14") (pin "17") (pinfunction "A4_17") (pintype "input"))
      (node (ref "H05") (pin "T2") (pinfunction "1_T2") (pintype "bidirectional"))
      (node (ref "SV3") (pin "42") (pinfunction "42_42") (pintype "passive"))
      (node (ref "SV5") (pin "42") (pinfunction "42_42") (pintype "passive"))
      (node (ref "U$5") (pin "T2") (pinfunction "P$1_T2") (pintype "passive"))
    )
    (net (code "34") (name "MCBMB00(0)") (class "Default")
      (node (ref "E13") (pin "2") (pinfunction "A1_2") (pintype "input"))
      (node (ref "H02") (pin "S2") (pinfunction "1_S2") (pintype "bidirectional"))
      (node (ref "SV2") (pin "38") (pinfunction "38_38") (pintype "passive"))
      (node (ref "SV3") (pin "38") (pinfunction "38_38") (pintype "passive"))
      (node (ref "U$2") (pin "S2") (pinfunction "P$1_S2") (pintype "passive"))
    )
    (net (code "35") (name "MCBMB01(0)") (class "Default")
      (node (ref "E13") (pin "4") (pinfunction "A2_4") (pintype "input"))
      (node (ref "H02") (pin "T2") (pinfunction "1_T2") (pintype "bidirectional"))
      (node (ref "SV2") (pin "35") (pinfunction "35_35") (pintype "passive"))
      (node (ref "SV3") (pin "35") (pinfunction "35_35") (pintype "passive"))
      (node (ref "U$2") (pin "T2") (pinfunction "P$1_T2") (pintype "passive"))
    )
    (net (code "36") (name "MCBMB02(0)") (class "Default")
      (node (ref "E13") (pin "6") (pinfunction "A3_6") (pintype "input"))
      (node (ref "H02") (pin "V2") (pinfunction "1_V2") (pintype "bidirectional"))
      (node (ref "SV2") (pin "36") (pinfunction "36_36") (pintype "passive"))
      (node (ref "SV3") (pin "36") (pinfunction "36_36") (pintype "passive"))
      (node (ref "U$2") (pin "V2") (pinfunction "P$1_V2") (pintype "passive"))
    )
    (net (code "37") (name "MCBMB03(0)") (class "Default")
      (node (ref "E13") (pin "8") (pinfunction "A4_8") (pintype "input"))
      (node (ref "H03") (pin "D2") (pinfunction "1_D2") (pintype "bidirectional"))
      (node (ref "U$3") (pin "D2") (pinfunction "P$1_D2") (pintype "passive"))
    )
    (net (code "38") (name "MCBMB04(0)") (class "Default")
      (node (ref "E13") (pin "11") (pinfunction "A1_11") (pintype "input"))
      (node (ref "H03") (pin "E2") (pinfunction "1_E2") (pintype "bidirectional"))
      (node (ref "U$3") (pin "E2") (pinfunction "P$1_E2") (pintype "passive"))
    )
    (net (code "39") (name "MCBMB05(0)") (class "Default")
      (node (ref "E13") (pin "13") (pinfunction "A2_13") (pintype "input"))
      (node (ref "H03") (pin "H2") (pinfunction "1_H2") (pintype "bidirectional"))
      (node (ref "U$3") (pin "H2") (pinfunction "P$1_H2") (pintype "passive"))
    )
    (net (code "40") (name "MCBMB06(0)") (class "Default")
      (node (ref "E13") (pin "15") (pinfunction "A3_15") (pintype "input"))
      (node (ref "H03") (pin "K2") (pinfunction "1_K2") (pintype "bidirectional"))
      (node (ref "U$3") (pin "K2") (pinfunction "P$1_K2") (pintype "passive"))
    )
    (net (code "41") (name "MCBMB07(0)") (class "Default")
      (node (ref "E13") (pin "17") (pinfunction "A4_17") (pintype "input"))
      (node (ref "H03") (pin "M2") (pinfunction "1_M2") (pintype "bidirectional"))
      (node (ref "U$3") (pin "M2") (pinfunction "P$1_M2") (pintype "passive"))
    )
    (net (code "42") (name "MCBMB08(0)") (class "Default")
      (node (ref "E14") (pin "2") (pinfunction "A1_2") (pintype "input"))
      (node (ref "H03") (pin "P2") (pinfunction "1_P2") (pintype "bidirectional"))
      (node (ref "U$3") (pin "P2") (pinfunction "P$1_P2") (pintype "passive"))
    )
    (net (code "43") (name "MCBMB09(0)") (class "Default")
      (node (ref "E14") (pin "4") (pinfunction "A2_4") (pintype "input"))
      (node (ref "H03") (pin "S2") (pinfunction "1_S2") (pintype "bidirectional"))
      (node (ref "U$3") (pin "S2") (pinfunction "P$1_S2") (pintype "passive"))
    )
    (net (code "44") (name "MCBMB10(0)") (class "Default")
      (node (ref "E14") (pin "6") (pinfunction "A3_6") (pintype "input"))
      (node (ref "H03") (pin "T2") (pinfunction "1_T2") (pintype "bidirectional"))
      (node (ref "U$3") (pin "T2") (pinfunction "P$1_T2") (pintype "passive"))
    )
    (net (code "45") (name "MCBMB11(0)") (class "Default")
      (node (ref "E14") (pin "8") (pinfunction "A4_8") (pintype "input"))
      (node (ref "H03") (pin "V2") (pinfunction "1_V2") (pintype "bidirectional"))
      (node (ref "U$3") (pin "V2") (pinfunction "P$1_V2") (pintype "passive"))
    )
    (net (code "46") (name "MEM00") (class "Default")
      (node (ref "E11") (pin "18") (pinfunction "Y1_18") (pintype "tri_state"))
      (node (ref "H04") (pin "E2") (pinfunction "1_E2") (pintype "bidirectional"))
      (node (ref "U$4") (pin "E2") (pinfunction "P$1_E2") (pintype "passive"))
    )
    (net (code "47") (name "MEM01") (class "Default")
      (node (ref "E11") (pin "16") (pinfunction "Y2_16") (pintype "tri_state"))
      (node (ref "H04") (pin "H2") (pinfunction "1_H2") (pintype "bidirectional"))
      (node (ref "U$4") (pin "H2") (pinfunction "P$1_H2") (pintype "passive"))
    )
    (net (code "48") (name "MEM02") (class "Default")
      (node (ref "E11") (pin "14") (pinfunction "Y3_14") (pintype "tri_state"))
      (node (ref "H04") (pin "K2") (pinfunction "1_K2") (pintype "bidirectional"))
      (node (ref "U$4") (pin "K2") (pinfunction "P$1_K2") (pintype "passive"))
    )
    (net (code "49") (name "MEM03") (class "Default")
      (node (ref "E11") (pin "12") (pinfunction "Y4_12") (pintype "tri_state"))
      (node (ref "H04") (pin "M2") (pinfunction "1_M2") (pintype "bidirectional"))
      (node (ref "U$4") (pin "M2") (pinfunction "P$1_M2") (pintype "passive"))
    )
    (net (code "50") (name "MEM04") (class "Default")
      (node (ref "E11") (pin "9") (pinfunction "Y1_9") (pintype "tri_state"))
      (node (ref "H04") (pin "P2") (pinfunction "1_P2") (pintype "bidirectional"))
      (node (ref "U$4") (pin "P2") (pinfunction "P$1_P2") (pintype "passive"))
    )
    (net (code "51") (name "MEM05") (class "Default")
      (node (ref "E11") (pin "7") (pinfunction "Y2_7") (pintype "tri_state"))
      (node (ref "H04") (pin "S2") (pinfunction "1_S2") (pintype "bidirectional"))
      (node (ref "U$4") (pin "S2") (pinfunction "P$1_S2") (pintype "passive"))
    )
    (net (code "52") (name "MEM06") (class "Default")
      (node (ref "E11") (pin "5") (pinfunction "Y3_5") (pintype "tri_state"))
      (node (ref "H04") (pin "T2") (pinfunction "1_T2") (pintype "bidirectional"))
      (node (ref "U$4") (pin "T2") (pinfunction "P$1_T2") (pintype "passive"))
    )
    (net (code "53") (name "MEM07") (class "Default")
      (node (ref "E11") (pin "3") (pinfunction "Y4_3") (pintype "tri_state"))
      (node (ref "H04") (pin "V2") (pinfunction "1_V2") (pintype "bidirectional"))
      (node (ref "U$4") (pin "V2") (pinfunction "P$1_V2") (pintype "passive"))
    )
    (net (code "54") (name "MEM08") (class "Default")
      (node (ref "E12") (pin "18") (pinfunction "Y1_18") (pintype "tri_state"))
      (node (ref "H05") (pin "D2") (pinfunction "1_D2") (pintype "bidirectional"))
      (node (ref "SV4") (pin "41") (pinfunction "41_41") (pintype "passive"))
      (node (ref "SV5") (pin "41") (pinfunction "41_41") (pintype "passive"))
      (node (ref "U$5") (pin "D2") (pinfunction "P$1_D2") (pintype "passive"))
    )
    (net (code "55") (name "MEM09") (class "Default")
      (node (ref "E12") (pin "16") (pinfunction "Y2_16") (pintype "tri_state"))
      (node (ref "H05") (pin "E2") (pinfunction "1_E2") (pintype "bidirectional"))
      (node (ref "SV4") (pin "39") (pinfunction "39_39") (pintype "passive"))
      (node (ref "SV5") (pin "39") (pinfunction "39_39") (pintype "passive"))
      (node (ref "U$5") (pin "E2") (pinfunction "P$1_E2") (pintype "passive"))
    )
    (net (code "56") (name "MEM10") (class "Default")
      (node (ref "E12") (pin "14") (pinfunction "Y3_14") (pintype "tri_state"))
      (node (ref "H05") (pin "H2") (pinfunction "1_H2") (pintype "bidirectional"))
      (node (ref "SV4") (pin "40") (pinfunction "40_40") (pintype "passive"))
      (node (ref "SV5") (pin "40") (pinfunction "40_40") (pintype "passive"))
      (node (ref "U$5") (pin "H2") (pinfunction "P$1_H2") (pintype "passive"))
    )
    (net (code "57") (name "MEM11") (class "Default")
      (node (ref "E12") (pin "12") (pinfunction "Y4_12") (pintype "tri_state"))
      (node (ref "H05") (pin "K2") (pinfunction "1_K2") (pintype "bidirectional"))
      (node (ref "SV4") (pin "37") (pinfunction "37_37") (pintype "passive"))
      (node (ref "SV5") (pin "37") (pinfunction "37_37") (pintype "passive"))
      (node (ref "U$5") (pin "K2") (pinfunction "P$1_K2") (pintype "passive"))
    )
    (net (code "58") (name "MEMDONE(1)") (class "Default")
      (node (ref "E8") (pin "5") (pinfunction "Q_5") (pintype "output"))
      (node (ref "H05") (pin "S2") (pinfunction "1_S2") (pintype "bidirectional"))
      (node (ref "U$5") (pin "S2") (pinfunction "P$1_S2") (pintype "passive"))
    )
    (net (code "59") (name "MEMSTART(0)") (class "Default")
      (node (ref "E3") (pin "1") (pinfunction "IN_1") (pintype "input"))
      (node (ref "H05") (pin "M2") (pinfunction "1_M2") (pintype "bidirectional"))
      (node (ref "U$5") (pin "M2") (pinfunction "P$1_M2") (pintype "passive"))
    )
    (net (code "60") (name "MEM_P") (class "Default")
      (node (ref "E12") (pin "9") (pinfunction "Y1_9") (pintype "tri_state"))
      (node (ref "H04") (pin "D2") (pinfunction "1_D2") (pintype "bidirectional"))
      (node (ref "U$4") (pin "D2") (pinfunction "P$1_D2") (pintype "passive"))
    )
    (net (code "61") (name "MS100") (class "Default")
      (node (ref "E10") (pin "11") (pinfunction "CLK_11") (pintype "input"))
      (node (ref "E3") (pin "2") (pinfunction "TAP2_2") (pintype "output"))
    )
    (net (code "62") (name "MS150") (class "Default")
      (node (ref "E10") (pin "4") (pinfunction "PRE_4") (pintype "input"))
      (node (ref "E3") (pin "6") (pinfunction "TAP3_6") (pintype "output"))
    )
    (net (code "63") (name "MS250") (class "Default")
      (node (ref "E2") (pin "1") (pinfunction "IN_1") (pintype "input"))
      (node (ref "E3") (pin "5") (pinfunction "TAP5_5") (pintype "output"))
    )
    (net (code "64") (name "MS350") (class "Default")
      (node (ref "E2") (pin "2") (pinfunction "TAP2_2") (pintype "output"))
      (node (ref "E9") (pin "4") (pinfunction "PRE_4") (pintype "input"))
    )
    (net (code "65") (name "MS400") (class "Default")
      (node (ref "E2") (pin "6") (pinfunction "TAP3_6") (pintype "output"))
      (node (ref "E9") (pin "1") (pinfunction "CLR_1") (pintype "input"))
    )
    (net (code "66") (name "MS500") (class "Default")
      (node (ref "E1") (pin "1") (pinfunction "IN_1") (pintype "input"))
      (node (ref "E2") (pin "5") (pinfunction "TAP5_5") (pintype "output"))
    )
    (net (code "67") (name "MS650") (class "Default")
      (node (ref "E1") (pin "6") (pinfunction "TAP3_6") (pintype "output"))
      (node (ref "E10") (pin "1") (pinfunction "CLR_1") (pintype "input"))
    )
    (net (code "68") (name "Net-(E17A-I0)") (class "Default")
      (node (ref "E17") (pin "1") (pinfunction "I0_1") (pintype "input"))
      (node (ref "FIELDS") (pin "2") (pinfunction "2_2") (pintype "passive"))
    )
    (net (code "69") (name "Net-(E17A-I1)") (class "Default")
      (node (ref "E17") (pin "2") (pinfunction "I1_2") (pintype "input"))
      (node (ref "FIELDS") (pin "4") (pinfunction "4_4") (pintype "passive"))
    )
    (net (code "70") (name "Net-(E17A-I2)") (class "Default")
      (node (ref "E17") (pin "3") (pinfunction "I2_3") (pintype "input"))
      (node (ref "FIELDS") (pin "6") (pinfunction "6_6") (pintype "passive"))
    )
    (net (code "71") (name "Net-(E17A-I3)") (class "Default")
      (node (ref "E17") (pin "4") (pinfunction "I3_4") (pintype "input"))
      (node (ref "FIELDS") (pin "8") (pinfunction "8_8") (pintype "passive"))
    )
    (net (code "72") (name "Net-(E17A-I4)") (class "Default")
      (node (ref "E17") (pin "5") (pinfunction "I4_5") (pintype "input"))
      (node (ref "FIELDS") (pin "10") (pinfunction "10_10") (pintype "passive"))
    )
    (net (code "73") (name "Net-(E17A-I5)") (class "Default")
      (node (ref "E17") (pin "6") (pinfunction "I5_6") (pintype "input"))
      (node (ref "FIELDS") (pin "12") (pinfunction "12_12") (pintype "passive"))
    )
    (net (code "74") (name "Net-(E17A-I6)") (class "Default")
      (node (ref "E17") (pin "11") (pinfunction "I6_11") (pintype "input"))
      (node (ref "FIELDS") (pin "16") (pinfunction "16_16") (pintype "passive"))
    )
    (net (code "75") (name "Net-(E17A-I7)") (class "Default")
      (node (ref "E17") (pin "12") (pinfunction "I7_12") (pintype "input"))
      (node (ref "FIELDS") (pin "14") (pinfunction "14_14") (pintype "passive"))
    )
    (net (code "76") (name "Net-(E18A-Y0)") (class "Default")
      (node (ref "E18") (pin "15") (pinfunction "Y0_15") (pintype "output"))
      (node (ref "FIELDS") (pin "1") (pinfunction "1_1") (pintype "passive"))
    )
    (net (code "77") (name "Net-(E18A-Y1)") (class "Default")
      (node (ref "E18") (pin "14") (pinfunction "Y1_14") (pintype "output"))
      (node (ref "FIELDS") (pin "3") (pinfunction "3_3") (pintype "passive"))
    )
    (net (code "78") (name "Net-(E18A-Y2)") (class "Default")
      (node (ref "E18") (pin "13") (pinfunction "Y2_13") (pintype "output"))
      (node (ref "FIELDS") (pin "5") (pinfunction "5_5") (pintype "passive"))
    )
    (net (code "79") (name "Net-(E18A-Y3)") (class "Default")
      (node (ref "E18") (pin "12") (pinfunction "Y3_12") (pintype "output"))
      (node (ref "FIELDS") (pin "7") (pinfunction "7_7") (pintype "passive"))
    )
    (net (code "80") (name "Net-(E18A-Y4)") (class "Default")
      (node (ref "E18") (pin "11") (pinfunction "Y4_11") (pintype "output"))
      (node (ref "FIELDS") (pin "9") (pinfunction "9_9") (pintype "passive"))
    )
    (net (code "81") (name "Net-(E18A-Y5)") (class "Default")
      (node (ref "E18") (pin "10") (pinfunction "Y5_10") (pintype "output"))
      (node (ref "FIELDS") (pin "11") (pinfunction "11_11") (pintype "passive"))
    )
    (net (code "82") (name "Net-(E18A-Y6)") (class "Default")
      (node (ref "E18") (pin "9") (pinfunction "Y6_9") (pintype "output"))
      (node (ref "FIELDS") (pin "13") (pinfunction "13_13") (pintype "passive"))
    )
    (net (code "83") (name "Net-(E18A-Y7)") (class "Default")
      (node (ref "E18") (pin "7") (pinfunction "Y7_7") (pintype "output"))
      (node (ref "FIELDS") (pin "15") (pinfunction "15_15") (pintype "passive"))
    )
    (net (code "84") (name "Net-(H01B-1)") (class "Default")
      (node (ref "H01") (pin "B2") (pinfunction "1_B2") (pintype "bidirectional"))
      (node (ref "U$1") (pin "B2") (pinfunction "P$1_B2") (pintype "passive"))
    )
    (net (code "85") (name "Net-(H01F-1)") (class "Default")
      (node (ref "H01") (pin "F2") (pinfunction "1_F2") (pintype "bidirectional"))
      (node (ref "U$1") (pin "F2") (pinfunction "P$1_F2") (pintype "passive"))
    )
    (net (code "86") (name "Net-(H01H-1)") (class "Default")
      (node (ref "H01") (pin "J2") (pinfunction "1_J2") (pintype "bidirectional"))
      (node (ref "U$1") (pin "J2") (pinfunction "P$1_J2") (pintype "passive"))
    )
    (net (code "87") (name "Net-(H01J-1)") (class "Default")
      (node (ref "H01") (pin "L2") (pinfunction "1_L2") (pintype "bidirectional"))
      (node (ref "U$1") (pin "L2") (pinfunction "P$1_L2") (pintype "passive"))
    )
    (net (code "88") (name "Net-(H01L-1)") (class "Default")
      (node (ref "H01") (pin "N2") (pinfunction "1_N2") (pintype "bidirectional"))
      (node (ref "U$1") (pin "N2") (pinfunction "P$1_N2") (pintype "passive"))
    )
    (net (code "89") (name "Net-(H01N-1)") (class "Default")
      (node (ref "H01") (pin "R2") (pinfunction "1_R2") (pintype "bidirectional"))
      (node (ref "U$1") (pin "R2") (pinfunction "P$1_R2") (pintype "passive"))
    )
    (net (code "90") (name "Net-(H01Q-1)") (class "Default")
      (node (ref "H01") (pin "U2") (pinfunction "1_U2") (pintype "bidirectional"))
      (node (ref "U$1") (pin "U2") (pinfunction "P$1_U2") (pintype "passive"))
    )
    (net (code "91") (name "Net-(H02B-1)") (class "Default")
      (node (ref "H02") (pin "B2") (pinfunction "1_B2") (pintype "bidirectional"))
      (node (ref "U$2") (pin "B2") (pinfunction "P$1_B2") (pintype "passive"))
    )
    (net (code "92") (name "Net-(H02F-1)") (class "Default")
      (node (ref "H02") (pin "F2") (pinfunction "1_F2") (pintype "bidirectional"))
      (node (ref "U$2") (pin "F2") (pinfunction "P$1_F2") (pintype "passive"))
    )
    (net (code "93") (name "Net-(H02H-1)") (class "Default")
      (node (ref "H02") (pin "J2") (pinfunction "1_J2") (pintype "bidirectional"))
      (node (ref "U$2") (pin "J2") (pinfunction "P$1_J2") (pintype "passive"))
    )
    (net (code "94") (name "Net-(H02J-1)") (class "Default")
      (node (ref "H02") (pin "L2") (pinfunction "1_L2") (pintype "bidirectional"))
      (node (ref "U$2") (pin "L2") (pinfunction "P$1_L2") (pintype "passive"))
    )
    (net (code "95") (name "Net-(H02L-1)") (class "Default")
      (node (ref "H02") (pin "N2") (pinfunction "1_N2") (pintype "bidirectional"))
      (node (ref "U$2") (pin "N2") (pinfunction "P$1_N2") (pintype "passive"))
    )
    (net (code "96") (name "Net-(H02N-1)") (class "Default")
      (node (ref "H02") (pin "R2") (pinfunction "1_R2") (pintype "bidirectional"))
      (node (ref "U$2") (pin "R2") (pinfunction "P$1_R2") (pintype "passive"))
    )
    (net (code "97") (name "Net-(H02Q-1)") (class "Default")
      (node (ref "H02") (pin "U2") (pinfunction "1_U2") (pintype "bidirectional"))
      (node (ref "U$2") (pin "U2") (pinfunction "P$1_U2") (pintype "passive"))
    )
    (net (code "98") (name "Net-(H03B-1)") (class "Default")
      (node (ref "H03") (pin "B2") (pinfunction "1_B2") (pintype "bidirectional"))
      (node (ref "U$3") (pin "B2") (pinfunction "P$1_B2") (pintype "passive"))
    )
    (net (code "99") (name "Net-(H03F-1)") (class "Default")
      (node (ref "H03") (pin "F2") (pinfunction "1_F2") (pintype "bidirectional"))
      (node (ref "U$3") (pin "F2") (pinfunction "P$1_F2") (pintype "passive"))
    )
    (net (code "100") (name "Net-(H03H-1)") (class "Default")
      (node (ref "H03") (pin "J2") (pinfunction "1_J2") (pintype "bidirectional"))
      (node (ref "U$3") (pin "J2") (pinfunction "P$1_J2") (pintype "passive"))
    )
    (net (code "101") (name "Net-(H03J-1)") (class "Default")
      (node (ref "H03") (pin "L2") (pinfunction "1_L2") (pintype "bidirectional"))
      (node (ref "U$3") (pin "L2") (pinfunction "P$1_L2") (pintype "passive"))
    )
    (net (code "102") (name "Net-(H03L-1)") (class "Default")
      (node (ref "H03") (pin "N2") (pinfunction "1_N2") (pintype "bidirectional"))
      (node (ref "U$3") (pin "N2") (pinfunction "P$1_N2") (pintype "passive"))
    )
    (net (code "103") (name "Net-(H03N-1)") (class "Default")
      (node (ref "H03") (pin "R2") (pinfunction "1_R2") (pintype "bidirectional"))
      (node (ref "U$3") (pin "R2") (pinfunction "P$1_R2") (pintype "passive"))
    )
    (net (code "104") (name "Net-(H03Q-1)") (class "Default")
      (node (ref "H03") (pin "U2") (pinfunction "1_U2") (pintype "bidirectional"))
      (node (ref "U$3") (pin "U2") (pinfunction "P$1_U2") (pintype "passive"))
    )
    (net (code "105") (name "Net-(H04B-1)") (class "Default")
      (node (ref "H04") (pin "B2") (pinfunction "1_B2") (pintype "bidirectional"))
      (node (ref "U$4") (pin "B2") (pinfunction "P$1_B2") (pintype "passive"))
    )
    (net (code "106") (name "Net-(H04F-1)") (class "Default")
      (node (ref "H04") (pin "F2") (pinfunction "1_F2") (pintype "bidirectional"))
      (node (ref "U$4") (pin "F2") (pinfunction "P$1_F2") (pintype "passive"))
    )
    (net (code "107") (name "Net-(H04H-1)") (class "Default")
      (node (ref "H04") (pin "J2") (pinfunction "1_J2") (pintype "bidirectional"))
      (node (ref "U$4") (pin "J2") (pinfunction "P$1_J2") (pintype "passive"))
    )
    (net (code "108") (name "Net-(H04J-1)") (class "Default")
      (node (ref "H04") (pin "L2") (pinfunction "1_L2") (pintype "bidirectional"))
      (node (ref "U$4") (pin "L2") (pinfunction "P$1_L2") (pintype "passive"))
    )
    (net (code "109") (name "Net-(H04L-1)") (class "Default")
      (node (ref "H04") (pin "N2") (pinfunction "1_N2") (pintype "bidirectional"))
      (node (ref "U$4") (pin "N2") (pinfunction "P$1_N2") (pintype "passive"))
    )
    (net (code "110") (name "Net-(H04N-1)") (class "Default")
      (node (ref "H04") (pin "R2") (pinfunction "1_R2") (pintype "bidirectional"))
      (node (ref "U$4") (pin "R2") (pinfunction "P$1_R2") (pintype "passive"))
    )
    (net (code "111") (name "Net-(H04Q-1)") (class "Default")
      (node (ref "H04") (pin "U2") (pinfunction "1_U2") (pintype "bidirectional"))
      (node (ref "U$4") (pin "U2") (pinfunction "P$1_U2") (pintype "passive"))
    )
    (net (code "112") (name "Net-(H05B-1)") (class "Default")
      (node (ref "H05") (pin "B2") (pinfunction "1_B2") (pintype "bidirectional"))
      (node (ref "U$5") (pin "B2") (pinfunction "P$1_B2") (pintype "passive"))
    )
    (net (code "113") (name "Net-(H05F-1)") (class "Default")
      (node (ref "H05") (pin "F2") (pinfunction "1_F2") (pintype "bidirectional"))
      (node (ref "U$5") (pin "F2") (pinfunction "P$1_F2") (pintype "passive"))
    )
    (net (code "114") (name "Net-(H05H-1)") (class "Default")
      (node (ref "H05") (pin "J2") (pinfunction "1_J2") (pintype "bidirectional"))
      (node (ref "U$5") (pin "J2") (pinfunction "P$1_J2") (pintype "passive"))
    )
    (net (code "115") (name "Net-(H05J-1)") (class "Default")
      (node (ref "H05") (pin "L2") (pinfunction "1_L2") (pintype "bidirectional"))
      (node (ref "U$5") (pin "L2") (pinfunction "P$1_L2") (pintype "passive"))
    )
    (net (code "116") (name "Net-(H05L-1)") (class "Default")
      (node (ref "H05") (pin "N2") (pinfunction "1_N2") (pintype "bidirectional"))
      (node (ref "U$5") (pin "N2") (pinfunction "P$1_N2") (pintype "passive"))
    )
    (net (code "117") (name "Net-(H05N-1)") (class "Default")
      (node (ref "H05") (pin "R2") (pinfunction "1_R2") (pintype "bidirectional"))
      (node (ref "U$5") (pin "R2") (pinfunction "P$1_R2") (pintype "passive"))
    )
    (net (code "118") (name "Net-(H05Q-1)") (class "Default")
      (node (ref "H05") (pin "U2") (pinfunction "1_U2") (pintype "bidirectional"))
      (node (ref "U$5") (pin "U2") (pinfunction "P$1_U2") (pintype "passive"))
    )
    (net (code "119") (name "OE(0)") (class "Default")
      (node (ref "E10") (pin "6") (pinfunction "~{Q}_6") (pintype "output"))
      (node (ref "E11") (pin "1") (pinfunction "G_1") (pintype "input"))
      (node (ref "E11") (pin "19") (pinfunction "G_19") (pintype "input"))
      (node (ref "E12") (pin "1") (pinfunction "G_1") (pintype "input"))
      (node (ref "E12") (pin "19") (pinfunction "G_19") (pintype "input"))
      (node (ref "E15") (pin "22") (pinfunction "~{OE}_22") (pintype "input"))
      (node (ref "E16") (pin "22") (pinfunction "~{OE}_22") (pintype "input"))
      (node (ref "SV2") (pin "22") (pinfunction "22_22") (pintype "passive"))
      (node (ref "SV4") (pin "22") (pinfunction "22_22") (pintype "passive"))
      (node (ref "SV5") (pin "22") (pinfunction "22_22") (pintype "passive"))
    )
    (net (code "120") (name "PARITY") (class "Default")
      (node (ref "E12") (pin "11") (pinfunction "A1_11") (pintype "input"))
      (node (ref "E12") (pin "13") (pinfunction "A2_13") (pintype "input"))
      (node (ref "E12") (pin "15") (pinfunction "A3_15") (pintype "input"))
      (node (ref "E12") (pin "17") (pinfunction "A4_17") (pintype "input"))
      (node (ref "E14") (pin "9") (pinfunction "Y1_9") (pintype "tri_state"))
      (node (ref "E15") (pin "16") (pinfunction "I/O4_16") (pintype "bidirectional"))
      (node (ref "SV2") (pin "3") (pinfunction "3_3") (pintype "passive"))
      (node (ref "SV3") (pin "3") (pinfunction "3_3") (pintype "passive"))
      (node (ref "SV4") (pin "3") (pinfunction "3_3") (pintype "passive"))
    )
    (net (code "121") (name "STROBE(0)") (class "Default")
      (node (ref "E9") (pin "6") (pinfunction "~{Q}_6") (pintype "output"))
      (node (ref "H05") (pin "P2") (pinfunction "1_P2") (pintype "bidirectional"))
      (node (ref "U$5") (pin "P2") (pinfunction "P$1_P2") (pintype "passive"))
    )
    (net (code "122") (name "TP150") (class "Default")
      (node (ref "E7") (pin "6") (pinfunction "TAP3_6") (pintype "output"))
      (node (ref "E9") (pin "10") (pinfunction "PRE_10") (pintype "input"))
    )
    (net (code "123") (name "TP250") (class "Default")
      (node (ref "E6") (pin "1") (pinfunction "IN_1") (pintype "input"))
      (node (ref "E7") (pin "5") (pinfunction "TAP5_5") (pintype "output"))
    )
    (net (code "124") (name "TP300") (class "Default")
      (node (ref "E6") (pin "7") (pinfunction "TAP1_7") (pintype "output"))
      (node (ref "E9") (pin "13") (pinfunction "CLR_13") (pintype "input"))
    )
    (net (code "125") (name "TP500") (class "Default")
      (node (ref "E10") (pin "13") (pinfunction "CLR_13") (pintype "input"))
      (node (ref "E5") (pin "1") (pinfunction "IN_1") (pintype "input"))
      (node (ref "E6") (pin "5") (pinfunction "TAP5_5") (pintype "output"))
      (node (ref "E8") (pin "4") (pinfunction "PRE_4") (pintype "input"))
    )
    (net (code "126") (name "TP550") (class "Default")
      (node (ref "E5") (pin "7") (pinfunction "TAP1_7") (pintype "output"))
      (node (ref "E8") (pin "1") (pinfunction "CLR_1") (pintype "input"))
    )
    (net (code "127") (name "VCC") (class "Default")
      (node (ref "C1") (pin "1") (pinfunction "1_1") (pintype "passive"))
      (node (ref "C2") (pin "1") (pinfunction "1_1") (pintype "passive"))
      (node (ref "C3") (pin "1") (pinfunction "1_1") (pintype "passive"))
      (node (ref "C4") (pin "1") (pinfunction "1_1") (pintype "passive"))
      (node (ref "C5") (pin "1") (pinfunction "1_1") (pintype "passive"))
      (node (ref "C6") (pin "1") (pinfunction "1_1") (pintype "passive"))
      (node (ref "C7") (pin "1") (pinfunction "1_1") (pintype "passive"))
      (node (ref "C8") (pin "1") (pinfunction "1_1") (pintype "passive"))
      (node (ref "C9") (pin "1") (pinfunction "1_1") (pintype "passive"))
      (node (ref "E10") (pin "10") (pinfunction "PRE_10") (pintype "input"))
      (node (ref "E15") (pin "28") (pinfunction "VCC_28") (pintype "power_in"))
      (node (ref "E16") (pin "28") (pinfunction "VCC_28") (pintype "power_in"))
      (node (ref "E18") (pin "6") (pinfunction "G1_6") (pintype "input"))
      (node (ref "H01") (pin "A2") (pinfunction "1_A2") (pintype "bidirectional"))
      (node (ref "H02") (pin "A2") (pinfunction "1_A2") (pintype "bidirectional"))
      (node (ref "H03") (pin "A2") (pinfunction "1_A2") (pintype "bidirectional"))
      (node (ref "H04") (pin "A2") (pinfunction "1_A2") (pintype "bidirectional"))
      (node (ref "H05") (pin "A2") (pinfunction "1_A2") (pintype "bidirectional"))
      (node (ref "U$1") (pin "A2") (pinfunction "P$1_A2") (pintype "passive"))
      (node (ref "U$2") (pin "A2") (pinfunction "P$1_A2") (pintype "passive"))
      (node (ref "U$3") (pin "A2") (pinfunction "P$1_A2") (pintype "passive"))
      (node (ref "U$4") (pin "A2") (pinfunction "P$1_A2") (pintype "passive"))
      (node (ref "U$5") (pin "A2") (pinfunction "P$1_A2") (pintype "passive"))
    )
    (net (code "128") (name "WE(0)") (class "Default")
      (node (ref "E13") (pin "1") (pinfunction "G_1") (pintype "input"))
      (node (ref "E13") (pin "19") (pinfunction "G_19") (pintype "input"))
      (node (ref "E14") (pin "1") (pinfunction "G_1") (pintype "input"))
      (node (ref "E14") (pin "19") (pinfunction "G_19") (pintype "input"))
      (node (ref "E15") (pin "27") (pinfunction "~{WE}_27") (pintype "input"))
      (node (ref "E16") (pin "27") (pinfunction "~{WE}_27") (pintype "input"))
      (node (ref "E9") (pin "8") (pinfunction "~{Q}_8") (pintype "output"))
      (node (ref "SV2") (pin "32") (pinfunction "32_32") (pintype "passive"))
      (node (ref "SV3") (pin "32") (pinfunction "32_32") (pintype "passive"))
      (node (ref "SV5") (pin "32") (pinfunction "32_32") (pintype "passive"))
    )
    (net (code "129") (name "unconnected-(E1A-TAP1-Pad7)") (class "Default")
      (node (ref "E1") (pin "7") (pinfunction "TAP1_7") (pintype "output"))
    )
    (net (code "130") (name "unconnected-(E1A-TAP2-Pad2)") (class "Default")
      (node (ref "E1") (pin "2") (pinfunction "TAP2_2") (pintype "output"))
    )
    (net (code "131") (name "unconnected-(E1A-TAP4-Pad3)") (class "Default")
      (node (ref "E1") (pin "3") (pinfunction "TAP4_3") (pintype "output"))
    )
    (net (code "132") (name "unconnected-(E1A-TAP5-Pad5)") (class "Default")
      (node (ref "E1") (pin "5") (pinfunction "TAP5_5") (pintype "output"))
    )
    (net (code "133") (name "unconnected-(E2A-TAP1-Pad7)") (class "Default")
      (node (ref "E2") (pin "7") (pinfunction "TAP1_7") (pintype "output"))
    )
    (net (code "134") (name "unconnected-(E2A-TAP4-Pad3)") (class "Default")
      (node (ref "E2") (pin "3") (pinfunction "TAP4_3") (pintype "output"))
    )
    (net (code "135") (name "unconnected-(E3A-TAP1-Pad7)") (class "Default")
      (node (ref "E3") (pin "7") (pinfunction "TAP1_7") (pintype "output"))
    )
    (net (code "136") (name "unconnected-(E3A-TAP4-Pad3)") (class "Default")
      (node (ref "E3") (pin "3") (pinfunction "TAP4_3") (pintype "output"))
    )
    (net (code "137") (name "unconnected-(E5A-TAP2-Pad2)") (class "Default")
      (node (ref "E5") (pin "2") (pinfunction "TAP2_2") (pintype "output"))
    )
    (net (code "138") (name "unconnected-(E5A-TAP3-Pad6)") (class "Default")
      (node (ref "E5") (pin "6") (pinfunction "TAP3_6") (pintype "output"))
    )
    (net (code "139") (name "unconnected-(E5A-TAP4-Pad3)") (class "Default")
      (node (ref "E5") (pin "3") (pinfunction "TAP4_3") (pintype "output"))
    )
    (net (code "140") (name "unconnected-(E5A-TAP5-Pad5)") (class "Default")
      (node (ref "E5") (pin "5") (pinfunction "TAP5_5") (pintype "output"))
    )
    (net (code "141") (name "unconnected-(E6A-TAP2-Pad2)") (class "Default")
      (node (ref "E6") (pin "2") (pinfunction "TAP2_2") (pintype "output"))
    )
    (net (code "142") (name "unconnected-(E6A-TAP3-Pad6)") (class "Default")
      (node (ref "E6") (pin "6") (pinfunction "TAP3_6") (pintype "output"))
    )
    (net (code "143") (name "unconnected-(E6A-TAP4-Pad3)") (class "Default")
      (node (ref "E6") (pin "3") (pinfunction "TAP4_3") (pintype "output"))
    )
    (net (code "144") (name "unconnected-(E7A-TAP1-Pad7)") (class "Default")
      (node (ref "E7") (pin "7") (pinfunction "TAP1_7") (pintype "output"))
    )
    (net (code "145") (name "unconnected-(E7A-TAP2-Pad2)") (class "Default")
      (node (ref "E7") (pin "2") (pinfunction "TAP2_2") (pintype "output"))
    )
    (net (code "146") (name "unconnected-(E7A-TAP4-Pad3)") (class "Default")
      (node (ref "E7") (pin "3") (pinfunction "TAP4_3") (pintype "output"))
    )
    (net (code "147") (name "unconnected-(E8A-~{Q}-Pad6)") (class "Default")
      (node (ref "E8") (pin "6") (pinfunction "~{Q}_6") (pintype "output"))
    )
    (net (code "148") (name "unconnected-(E9A-Q-Pad5)") (class "Default")
      (node (ref "E9") (pin "5") (pinfunction "Q_5") (pintype "output"))
    )
    (net (code "149") (name "unconnected-(E9B-Q-Pad9)") (class "Default")
      (node (ref "E9") (pin "9") (pinfunction "Q_9") (pintype "output"))
    )
    (net (code "150") (name "unconnected-(E10A-Q-Pad5)") (class "Default")
      (node (ref "E10") (pin "5") (pinfunction "Q_5") (pintype "output"))
    )
    (net (code "151") (name "unconnected-(E10B-Q-Pad9)") (class "Default")
      (node (ref "E10") (pin "9") (pinfunction "Q_9") (pintype "output"))
    )
    (net (code "152") (name "unconnected-(E12B-Y2-Pad7)") (class "Default")
      (node (ref "E12") (pin "7") (pinfunction "Y2_7") (pintype "tri_state"))
    )
    (net (code "153") (name "unconnected-(E12B-Y3-Pad5)") (class "Default")
      (node (ref "E12") (pin "5") (pinfunction "Y3_5") (pintype "tri_state"))
    )
    (net (code "154") (name "unconnected-(E12B-Y4-Pad3)") (class "Default")
      (node (ref "E12") (pin "3") (pinfunction "Y4_3") (pintype "tri_state"))
    )
    (net (code "155") (name "unconnected-(E14B-Y2-Pad7)") (class "Default")
      (node (ref "E14") (pin "7") (pinfunction "Y2_7") (pintype "tri_state"))
    )
    (net (code "156") (name "unconnected-(E14B-Y3-Pad5)") (class "Default")
      (node (ref "E14") (pin "5") (pinfunction "Y3_5") (pintype "tri_state"))
    )
    (net (code "157") (name "unconnected-(E14B-Y4-Pad3)") (class "Default")
      (node (ref "E14") (pin "3") (pinfunction "Y4_3") (pintype "tri_state"))
    )
    (net (code "158") (name "unconnected-(E15-I{slash}O5-Pad17)") (class "Default")
      (node (ref "E15") (pin "17") (pinfunction "I/O5_17") (pintype "bidirectional"))
    )
    (net (code "159") (name "unconnected-(E15-I{slash}O6-Pad18)") (class "Default")
      (node (ref "E15") (pin "18") (pinfunction "I/O6_18") (pintype "bidirectional"))
    )
    (net (code "160") (name "unconnected-(E15-I{slash}O7-Pad19)") (class "Default")
      (node (ref "E15") (pin "19") (pinfunction "I/O7_19") (pintype "bidirectional"))
    )
    (net (code "161") (name "unconnected-(SV1-Pad3)") (class "Default")
      (node (ref "SV1") (pin "3") (pinfunction "3_3") (pintype "passive"))
    )
    (net (code "162") (name "unconnected-(SV1-Pad4)") (class "Default")
      (node (ref "SV1") (pin "4") (pinfunction "4_4") (pintype "passive"))
    )
    (net (code "163") (name "unconnected-(SV1-Pad5)") (class "Default")
      (node (ref "SV1") (pin "5") (pinfunction "5_5") (pintype "passive"))
    )
    (net (code "164") (name "unconnected-(SV1-Pad6)") (class "Default")
      (node (ref "SV1") (pin "6") (pinfunction "6_6") (pintype "passive"))
    )
    (net (code "165") (name "unconnected-(SV1-Pad7)") (class "Default")
      (node (ref "SV1") (pin "7") (pinfunction "7_7") (pintype "passive"))
    )
    (net (code "166") (name "unconnected-(SV1-Pad8)") (class "Default")
      (node (ref "SV1") (pin "8") (pinfunction "8_8") (pintype "passive"))
    )
    (net (code "167") (name "unconnected-(SV1-Pad9)") (class "Default")
      (node (ref "SV1") (pin "9") (pinfunction "9_9") (pintype "passive"))
    )
    (net (code "168") (name "unconnected-(SV1-Pad10)") (class "Default")
      (node (ref "SV1") (pin "10") (pinfunction "10_10") (pintype "passive"))
    )
    (net (code "169") (name "unconnected-(SV1-Pad11)") (class "Default")
      (node (ref "SV1") (pin "11") (pinfunction "11_11") (pintype "passive"))
    )
    (net (code "170") (name "unconnected-(SV1-Pad12)") (class "Default")
      (node (ref "SV1") (pin "12") (pinfunction "12_12") (pintype "passive"))
    )
    (net (code "171") (name "unconnected-(SV1-Pad13)") (class "Default")
      (node (ref "SV1") (pin "13") (pinfunction "13_13") (pintype "passive"))
    )
    (net (code "172") (name "unconnected-(SV1-Pad14)") (class "Default")
      (node (ref "SV1") (pin "14") (pinfunction "14_14") (pintype "passive"))
    )
    (net (code "173") (name "unconnected-(SV1-Pad15)") (class "Default")
      (node (ref "SV1") (pin "15") (pinfunction "15_15") (pintype "passive"))
    )
    (net (code "174") (name "unconnected-(SV1-Pad16)") (class "Default")
      (node (ref "SV1") (pin "16") (pinfunction "16_16") (pintype "passive"))
    )
    (net (code "175") (name "unconnected-(SV1-Pad17)") (class "Default")
      (node (ref "SV1") (pin "17") (pinfunction "17_17") (pintype "passive"))
    )
    (net (code "176") (name "unconnected-(SV1-Pad18)") (class "Default")
      (node (ref "SV1") (pin "18") (pinfunction "18_18") (pintype "passive"))
    )
    (net (code "177") (name "unconnected-(SV1-Pad19)") (class "Default")
      (node (ref "SV1") (pin "19") (pinfunction "19_19") (pintype "passive"))
    )
    (net (code "178") (name "unconnected-(SV1-Pad21)") (class "Default")
      (node (ref "SV1") (pin "21") (pinfunction "21_21") (pintype "passive"))
    )
    (net (code "179") (name "unconnected-(SV1-Pad22)") (class "Default")
      (node (ref "SV1") (pin "22") (pinfunction "22_22") (pintype "passive"))
    )
    (net (code "180") (name "unconnected-(SV1-Pad23)") (class "Default")
      (node (ref "SV1") (pin "23") (pinfunction "23_23") (pintype "passive"))
    )
    (net (code "181") (name "unconnected-(SV1-Pad25)") (class "Default")
      (node (ref "SV1") (pin "25") (pinfunction "25_25") (pintype "passive"))
    )
    (net (code "182") (name "unconnected-(SV1-Pad32)") (class "Default")
      (node (ref "SV1") (pin "32") (pinfunction "32_32") (pintype "passive"))
    )
    (net (code "183") (name "unconnected-(SV1-Pad35)") (class "Default")
      (node (ref "SV1") (pin "35") (pinfunction "35_35") (pintype "passive"))
    )
    (net (code "184") (name "unconnected-(SV1-Pad36)") (class "Default")
      (node (ref "SV1") (pin "36") (pinfunction "36_36") (pintype "passive"))
    )
    (net (code "185") (name "unconnected-(SV1-Pad37)") (class "Default")
      (node (ref "SV1") (pin "37") (pinfunction "37_37") (pintype "passive"))
    )
    (net (code "186") (name "unconnected-(SV1-Pad38)") (class "Default")
      (node (ref "SV1") (pin "38") (pinfunction "38_38") (pintype "passive"))
    )
    (net (code "187") (name "unconnected-(SV1-Pad39)") (class "Default")
      (node (ref "SV1") (pin "39") (pinfunction "39_39") (pintype "passive"))
    )
    (net (code "188") (name "unconnected-(SV1-Pad40)") (class "Default")
      (node (ref "SV1") (pin "40") (pinfunction "40_40") (pintype "passive"))
    )
    (net (code "189") (name "unconnected-(SV1-Pad41)") (class "Default")
      (node (ref "SV1") (pin "41") (pinfunction "41_41") (pintype "passive"))
    )
    (net (code "190") (name "unconnected-(SV1-Pad42)") (class "Default")
      (node (ref "SV1") (pin "42") (pinfunction "42_42") (pintype "passive"))
    )
    (net (code "191") (name "unconnected-(SV1-Pad43)") (class "Default")
      (node (ref "SV1") (pin "43") (pinfunction "43_43") (pintype "passive"))
    )
    (net (code "192") (name "unconnected-(SV1-Pad44)") (class "Default")
      (node (ref "SV1") (pin "44") (pinfunction "44_44") (pintype "passive"))
    )
    (net (code "193") (name "unconnected-(SV1-Pad45)") (class "Default")
      (node (ref "SV1") (pin "45") (pinfunction "45_45") (pintype "passive"))
    )
    (net (code "194") (name "unconnected-(SV1-Pad46)") (class "Default")
      (node (ref "SV1") (pin "46") (pinfunction "46_46") (pintype "passive"))
    )
    (net (code "195") (name "unconnected-(SV1-Pad47)") (class "Default")
      (node (ref "SV1") (pin "47") (pinfunction "47_47") (pintype "passive"))
    )
    (net (code "196") (name "unconnected-(SV1-Pad48)") (class "Default")
      (node (ref "SV1") (pin "48") (pinfunction "48_48") (pintype "passive"))
    )
    (net (code "197") (name "unconnected-(SV2-Pad34)") (class "Default")
      (node (ref "SV2") (pin "34") (pinfunction "34_34") (pintype "passive"))
    )
    (net (code "198") (name "unconnected-(SV2-Pad37)") (class "Default")
      (node (ref "SV2") (pin "37") (pinfunction "37_37") (pintype "passive"))
    )
    (net (code "199") (name "unconnected-(SV2-Pad39)") (class "Default")
      (node (ref "SV2") (pin "39") (pinfunction "39_39") (pintype "passive"))
    )
    (net (code "200") (name "unconnected-(SV2-Pad40)") (class "Default")
      (node (ref "SV2") (pin "40") (pinfunction "40_40") (pintype "passive"))
    )
    (net (code "201") (name "unconnected-(SV2-Pad41)") (class "Default")
      (node (ref "SV2") (pin "41") (pinfunction "41_41") (pintype "passive"))
    )
    (net (code "202") (name "unconnected-(SV2-Pad42)") (class "Default")
      (node (ref "SV2") (pin "42") (pinfunction "42_42") (pintype "passive"))
    )
    (net (code "203") (name "unconnected-(SV2-Pad43)") (class "Default")
      (node (ref "SV2") (pin "43") (pinfunction "43_43") (pintype "passive"))
    )
    (net (code "204") (name "unconnected-(SV2-Pad44)") (class "Default")
      (node (ref "SV2") (pin "44") (pinfunction "44_44") (pintype "passive"))
    )
    (net (code "205") (name "unconnected-(SV2-Pad45)") (class "Default")
      (node (ref "SV2") (pin "45") (pinfunction "45_45") (pintype "passive"))
    )
    (net (code "206") (name "unconnected-(SV2-Pad46)") (class "Default")
      (node (ref "SV2") (pin "46") (pinfunction "46_46") (pintype "passive"))
    )
    (net (code "207") (name "unconnected-(SV2-Pad47)") (class "Default")
      (node (ref "SV2") (pin "47") (pinfunction "47_47") (pintype "passive"))
    )
    (net (code "208") (name "unconnected-(SV2-Pad48)") (class "Default")
      (node (ref "SV2") (pin "48") (pinfunction "48_48") (pintype "passive"))
    )
    (net (code "209") (name "unconnected-(SV3-Pad15)") (class "Default")
      (node (ref "SV3") (pin "15") (pinfunction "15_15") (pintype "passive"))
    )
    (net (code "210") (name "unconnected-(SV3-Pad17)") (class "Default")
      (node (ref "SV3") (pin "17") (pinfunction "17_17") (pintype "passive"))
    )
    (net (code "211") (name "unconnected-(SV3-Pad18)") (class "Default")
      (node (ref "SV3") (pin "18") (pinfunction "18_18") (pintype "passive"))
    )
    (net (code "212") (name "unconnected-(SV3-Pad19)") (class "Default")
      (node (ref "SV3") (pin "19") (pinfunction "19_19") (pintype "passive"))
    )
    (net (code "213") (name "unconnected-(SV3-Pad20)") (class "Default")
      (node (ref "SV3") (pin "20") (pinfunction "20_20") (pintype "passive"))
    )
    (net (code "214") (name "unconnected-(SV3-Pad21)") (class "Default")
      (node (ref "SV3") (pin "21") (pinfunction "21_21") (pintype "passive"))
    )
    (net (code "215") (name "unconnected-(SV3-Pad22)") (class "Default")
      (node (ref "SV3") (pin "22") (pinfunction "22_22") (pintype "passive"))
    )
    (net (code "216") (name "unconnected-(SV3-Pad23)") (class "Default")
      (node (ref "SV3") (pin "23") (pinfunction "23_23") (pintype "passive"))
    )
    (net (code "217") (name "unconnected-(SV3-Pad24)") (class "Default")
      (node (ref "SV3") (pin "24") (pinfunction "24_24") (pintype "passive"))
    )
    (net (code "218") (name "unconnected-(SV3-Pad25)") (class "Default")
      (node (ref "SV3") (pin "25") (pinfunction "25_25") (pintype "passive"))
    )
    (net (code "219") (name "unconnected-(SV3-Pad26)") (class "Default")
      (node (ref "SV3") (pin "26") (pinfunction "26_26") (pintype "passive"))
    )
    (net (code "220") (name "unconnected-(SV3-Pad27)") (class "Default")
      (node (ref "SV3") (pin "27") (pinfunction "27_27") (pintype "passive"))
    )
    (net (code "221") (name "unconnected-(SV3-Pad28)") (class "Default")
      (node (ref "SV3") (pin "28") (pinfunction "28_28") (pintype "passive"))
    )
    (net (code "222") (name "unconnected-(SV3-Pad29)") (class "Default")
      (node (ref "SV3") (pin "29") (pinfunction "29_29") (pintype "passive"))
    )
    (net (code "223") (name "unconnected-(SV3-Pad30)") (class "Default")
      (node (ref "SV3") (pin "30") (pinfunction "30_30") (pintype "passive"))
    )
    (net (code "224") (name "unconnected-(SV3-Pad31)") (class "Default")
      (node (ref "SV3") (pin "31") (pinfunction "31_31") (pintype "passive"))
    )
    (net (code "225") (name "unconnected-(SV3-Pad33)") (class "Default")
      (node (ref "SV3") (pin "33") (pinfunction "33_33") (pintype "passive"))
    )
    (net (code "226") (name "unconnected-(SV3-Pad34)") (class "Default")
      (node (ref "SV3") (pin "34") (pinfunction "34_34") (pintype "passive"))
    )
    (net (code "227") (name "unconnected-(SV3-Pad37)") (class "Default")
      (node (ref "SV3") (pin "37") (pinfunction "37_37") (pintype "passive"))
    )
    (net (code "228") (name "unconnected-(SV3-Pad39)") (class "Default")
      (node (ref "SV3") (pin "39") (pinfunction "39_39") (pintype "passive"))
    )
    (net (code "229") (name "unconnected-(SV3-Pad40)") (class "Default")
      (node (ref "SV3") (pin "40") (pinfunction "40_40") (pintype "passive"))
    )
    (net (code "230") (name "unconnected-(SV3-Pad41)") (class "Default")
      (node (ref "SV3") (pin "41") (pinfunction "41_41") (pintype "passive"))
    )
    (net (code "231") (name "unconnected-(SV3-Pad43)") (class "Default")
      (node (ref "SV3") (pin "43") (pinfunction "43_43") (pintype "passive"))
    )
    (net (code "232") (name "unconnected-(SV3-Pad44)") (class "Default")
      (node (ref "SV3") (pin "44") (pinfunction "44_44") (pintype "passive"))
    )
    (net (code "233") (name "unconnected-(SV3-Pad45)") (class "Default")
      (node (ref "SV3") (pin "45") (pinfunction "45_45") (pintype "passive"))
    )
    (net (code "234") (name "unconnected-(SV3-Pad46)") (class "Default")
      (node (ref "SV3") (pin "46") (pinfunction "46_46") (pintype "passive"))
    )
    (net (code "235") (name "unconnected-(SV3-Pad47)") (class "Default")
      (node (ref "SV3") (pin "47") (pinfunction "47_47") (pintype "passive"))
    )
    (net (code "236") (name "unconnected-(SV3-Pad48)") (class "Default")
      (node (ref "SV3") (pin "48") (pinfunction "48_48") (pintype "passive"))
    )
    (net (code "237") (name "unconnected-(SV4-Pad15)") (class "Default")
      (node (ref "SV4") (pin "15") (pinfunction "15_15") (pintype "passive"))
    )
    (net (code "238") (name "unconnected-(SV4-Pad17)") (class "Default")
      (node (ref "SV4") (pin "17") (pinfunction "17_17") (pintype "passive"))
    )
    (net (code "239") (name "unconnected-(SV4-Pad18)") (class "Default")
      (node (ref "SV4") (pin "18") (pinfunction "18_18") (pintype "passive"))
    )
    (net (code "240") (name "unconnected-(SV4-Pad19)") (class "Default")
      (node (ref "SV4") (pin "19") (pinfunction "19_19") (pintype "passive"))
    )
    (net (code "241") (name "unconnected-(SV4-Pad20)") (class "Default")
      (node (ref "SV4") (pin "20") (pinfunction "20_20") (pintype "passive"))
    )
    (net (code "242") (name "unconnected-(SV4-Pad21)") (class "Default")
      (node (ref "SV4") (pin "21") (pinfunction "21_21") (pintype "passive"))
    )
    (net (code "243") (name "unconnected-(SV4-Pad23)") (class "Default")
      (node (ref "SV4") (pin "23") (pinfunction "23_23") (pintype "passive"))
    )
    (net (code "244") (name "unconnected-(SV4-Pad24)") (class "Default")
      (node (ref "SV4") (pin "24") (pinfunction "24_24") (pintype "passive"))
    )
    (net (code "245") (name "unconnected-(SV4-Pad25)") (class "Default")
      (node (ref "SV4") (pin "25") (pinfunction "25_25") (pintype "passive"))
    )
    (net (code "246") (name "unconnected-(SV4-Pad26)") (class "Default")
      (node (ref "SV4") (pin "26") (pinfunction "26_26") (pintype "passive"))
    )
    (net (code "247") (name "unconnected-(SV4-Pad27)") (class "Default")
      (node (ref "SV4") (pin "27") (pinfunction "27_27") (pintype "passive"))
    )
    (net (code "248") (name "unconnected-(SV4-Pad28)") (class "Default")
      (node (ref "SV4") (pin "28") (pinfunction "28_28") (pintype "passive"))
    )
    (net (code "249") (name "unconnected-(SV4-Pad29)") (class "Default")
      (node (ref "SV4") (pin "29") (pinfunction "29_29") (pintype "passive"))
    )
    (net (code "250") (name "unconnected-(SV4-Pad30)") (class "Default")
      (node (ref "SV4") (pin "30") (pinfunction "30_30") (pintype "passive"))
    )
    (net (code "251") (name "unconnected-(SV4-Pad31)") (class "Default")
      (node (ref "SV4") (pin "31") (pinfunction "31_31") (pintype "passive"))
    )
    (net (code "252") (name "unconnected-(SV4-Pad32)") (class "Default")
      (node (ref "SV4") (pin "32") (pinfunction "32_32") (pintype "passive"))
    )
    (net (code "253") (name "unconnected-(SV4-Pad33)") (class "Default")
      (node (ref "SV4") (pin "33") (pinfunction "33_33") (pintype "passive"))
    )
    (net (code "254") (name "unconnected-(SV4-Pad34)") (class "Default")
      (node (ref "SV4") (pin "34") (pinfunction "34_34") (pintype "passive"))
    )
    (net (code "255") (name "unconnected-(SV4-Pad35)") (class "Default")
      (node (ref "SV4") (pin "35") (pinfunction "35_35") (pintype "passive"))
    )
    (net (code "256") (name "unconnected-(SV4-Pad36)") (class "Default")
      (node (ref "SV4") (pin "36") (pinfunction "36_36") (pintype "passive"))
    )
    (net (code "257") (name "unconnected-(SV4-Pad38)") (class "Default")
      (node (ref "SV4") (pin "38") (pinfunction "38_38") (pintype "passive"))
    )
    (net (code "258") (name "unconnected-(SV4-Pad42)") (class "Default")
      (node (ref "SV4") (pin "42") (pinfunction "42_42") (pintype "passive"))
    )
    (net (code "259") (name "unconnected-(SV4-Pad43)") (class "Default")
      (node (ref "SV4") (pin "43") (pinfunction "43_43") (pintype "passive"))
    )
    (net (code "260") (name "unconnected-(SV4-Pad44)") (class "Default")
      (node (ref "SV4") (pin "44") (pinfunction "44_44") (pintype "passive"))
    )
    (net (code "261") (name "unconnected-(SV4-Pad45)") (class "Default")
      (node (ref "SV4") (pin "45") (pinfunction "45_45") (pintype "passive"))
    )
    (net (code "262") (name "unconnected-(SV4-Pad46)") (class "Default")
      (node (ref "SV4") (pin "46") (pinfunction "46_46") (pintype "passive"))
    )
    (net (code "263") (name "unconnected-(SV4-Pad47)") (class "Default")
      (node (ref "SV4") (pin "47") (pinfunction "47_47") (pintype "passive"))
    )
    (net (code "264") (name "unconnected-(SV4-Pad48)") (class "Default")
      (node (ref "SV4") (pin "48") (pinfunction "48_48") (pintype "passive"))
    )
    (net (code "265") (name "unconnected-(SV5-Pad3)") (class "Default")
      (node (ref "SV5") (pin "3") (pinfunction "3_3") (pintype "passive"))
    )
    (net (code "266") (name "unconnected-(SV5-Pad4)") (class "Default")
      (node (ref "SV5") (pin "4") (pinfunction "4_4") (pintype "passive"))
    )
    (net (code "267") (name "unconnected-(SV5-Pad5)") (class "Default")
      (node (ref "SV5") (pin "5") (pinfunction "5_5") (pintype "passive"))
    )
    (net (code "268") (name "unconnected-(SV5-Pad6)") (class "Default")
      (node (ref "SV5") (pin "6") (pinfunction "6_6") (pintype "passive"))
    )
    (net (code "269") (name "unconnected-(SV5-Pad7)") (class "Default")
      (node (ref "SV5") (pin "7") (pinfunction "7_7") (pintype "passive"))
    )
    (net (code "270") (name "unconnected-(SV5-Pad8)") (class "Default")
      (node (ref "SV5") (pin "8") (pinfunction "8_8") (pintype "passive"))
    )
    (net (code "271") (name "unconnected-(SV5-Pad9)") (class "Default")
      (node (ref "SV5") (pin "9") (pinfunction "9_9") (pintype "passive"))
    )
    (net (code "272") (name "unconnected-(SV5-Pad10)") (class "Default")
      (node (ref "SV5") (pin "10") (pinfunction "10_10") (pintype "passive"))
    )
    (net (code "273") (name "unconnected-(SV5-Pad11)") (class "Default")
      (node (ref "SV5") (pin "11") (pinfunction "11_11") (pintype "passive"))
    )
    (net (code "274") (name "unconnected-(SV5-Pad12)") (class "Default")
      (node (ref "SV5") (pin "12") (pinfunction "12_12") (pintype "passive"))
    )
    (net (code "275") (name "unconnected-(SV5-Pad13)") (class "Default")
      (node (ref "SV5") (pin "13") (pinfunction "13_13") (pintype "passive"))
    )
    (net (code "276") (name "unconnected-(SV5-Pad14)") (class "Default")
      (node (ref "SV5") (pin "14") (pinfunction "14_14") (pintype "passive"))
    )
    (net (code "277") (name "unconnected-(SV5-Pad15)") (class "Default")
      (node (ref "SV5") (pin "15") (pinfunction "15_15") (pintype "passive"))
    )
    (net (code "278") (name "unconnected-(SV5-Pad16)") (class "Default")
      (node (ref "SV5") (pin "16") (pinfunction "16_16") (pintype "passive"))
    )
    (net (code "279") (name "unconnected-(SV5-Pad17)") (class "Default")
      (node (ref "SV5") (pin "17") (pinfunction "17_17") (pintype "passive"))
    )
    (net (code "280") (name "unconnected-(SV5-Pad19)") (class "Default")
      (node (ref "SV5") (pin "19") (pinfunction "19_19") (pintype "passive"))
    )
    (net (code "281") (name "unconnected-(SV5-Pad20)") (class "Default")
      (node (ref "SV5") (pin "20") (pinfunction "20_20") (pintype "passive"))
    )
    (net (code "282") (name "unconnected-(SV5-Pad21)") (class "Default")
      (node (ref "SV5") (pin "21") (pinfunction "21_21") (pintype "passive"))
    )
    (net (code "283") (name "unconnected-(SV5-Pad23)") (class "Default")
      (node (ref "SV5") (pin "23") (pinfunction "23_23") (pintype "passive"))
    )
    (net (code "284") (name "unconnected-(SV5-Pad24)") (class "Default")
      (node (ref "SV5") (pin "24") (pinfunction "24_24") (pintype "passive"))
    )
    (net (code "285") (name "unconnected-(SV5-Pad25)") (class "Default")
      (node (ref "SV5") (pin "25") (pinfunction "25_25") (pintype "passive"))
    )
    (net (code "286") (name "unconnected-(SV5-Pad26)") (class "Default")
      (node (ref "SV5") (pin "26") (pinfunction "26_26") (pintype "passive"))
    )
    (net (code "287") (name "unconnected-(SV5-Pad27)") (class "Default")
      (node (ref "SV5") (pin "27") (pinfunction "27_27") (pintype "passive"))
    )
    (net (code "288") (name "unconnected-(SV5-Pad28)") (class "Default")
      (node (ref "SV5") (pin "28") (pinfunction "28_28") (pintype "passive"))
    )
    (net (code "289") (name "unconnected-(SV5-Pad29)") (class "Default")
      (node (ref "SV5") (pin "29") (pinfunction "29_29") (pintype "passive"))
    )
    (net (code "290") (name "unconnected-(SV5-Pad30)") (class "Default")
      (node (ref "SV5") (pin "30") (pinfunction "30_30") (pintype "passive"))
    )
    (net (code "291") (name "unconnected-(SV5-Pad31)") (class "Default")
      (node (ref "SV5") (pin "31") (pinfunction "31_31") (pintype "passive"))
    )
    (net (code "292") (name "unconnected-(SV5-Pad33)") (class "Default")
      (node (ref "SV5") (pin "33") (pinfunction "33_33") (pintype "passive"))
    )
    (net (code "293") (name "unconnected-(SV5-Pad35)") (class "Default")
      (node (ref "SV5") (pin "35") (pinfunction "35_35") (pintype "passive"))
    )
    (net (code "294") (name "unconnected-(SV5-Pad36)") (class "Default")
      (node (ref "SV5") (pin "36") (pinfunction "36_36") (pintype "passive"))
    )
    (net (code "295") (name "unconnected-(SV5-Pad38)") (class "Default")
      (node (ref "SV5") (pin "38") (pinfunction "38_38") (pintype "passive"))
    )
    (net (code "296") (name "unconnected-(SV5-Pad43)") (class "Default")
      (node (ref "SV5") (pin "43") (pinfunction "43_43") (pintype "passive"))
    )
    (net (code "297") (name "unconnected-(SV5-Pad44)") (class "Default")
      (node (ref "SV5") (pin "44") (pinfunction "44_44") (pintype "passive"))
    )
    (net (code "298") (name "unconnected-(SV5-Pad45)") (class "Default")
      (node (ref "SV5") (pin "45") (pinfunction "45_45") (pintype "passive"))
    )
    (net (code "299") (name "unconnected-(SV5-Pad46)") (class "Default")
      (node (ref "SV5") (pin "46") (pinfunction "46_46") (pintype "passive"))
    )
    (net (code "300") (name "unconnected-(SV5-Pad47)") (class "Default")
      (node (ref "SV5") (pin "47") (pinfunction "47_47") (pintype "passive"))
    )
    (net (code "301") (name "unconnected-(SV5-Pad48)") (class "Default")
      (node (ref "SV5") (pin "48") (pinfunction "48_48") (pintype "passive"))
    )
  )
)
